# test_eyes.net
KiCad netlist of a schematic drawn in EAGLE
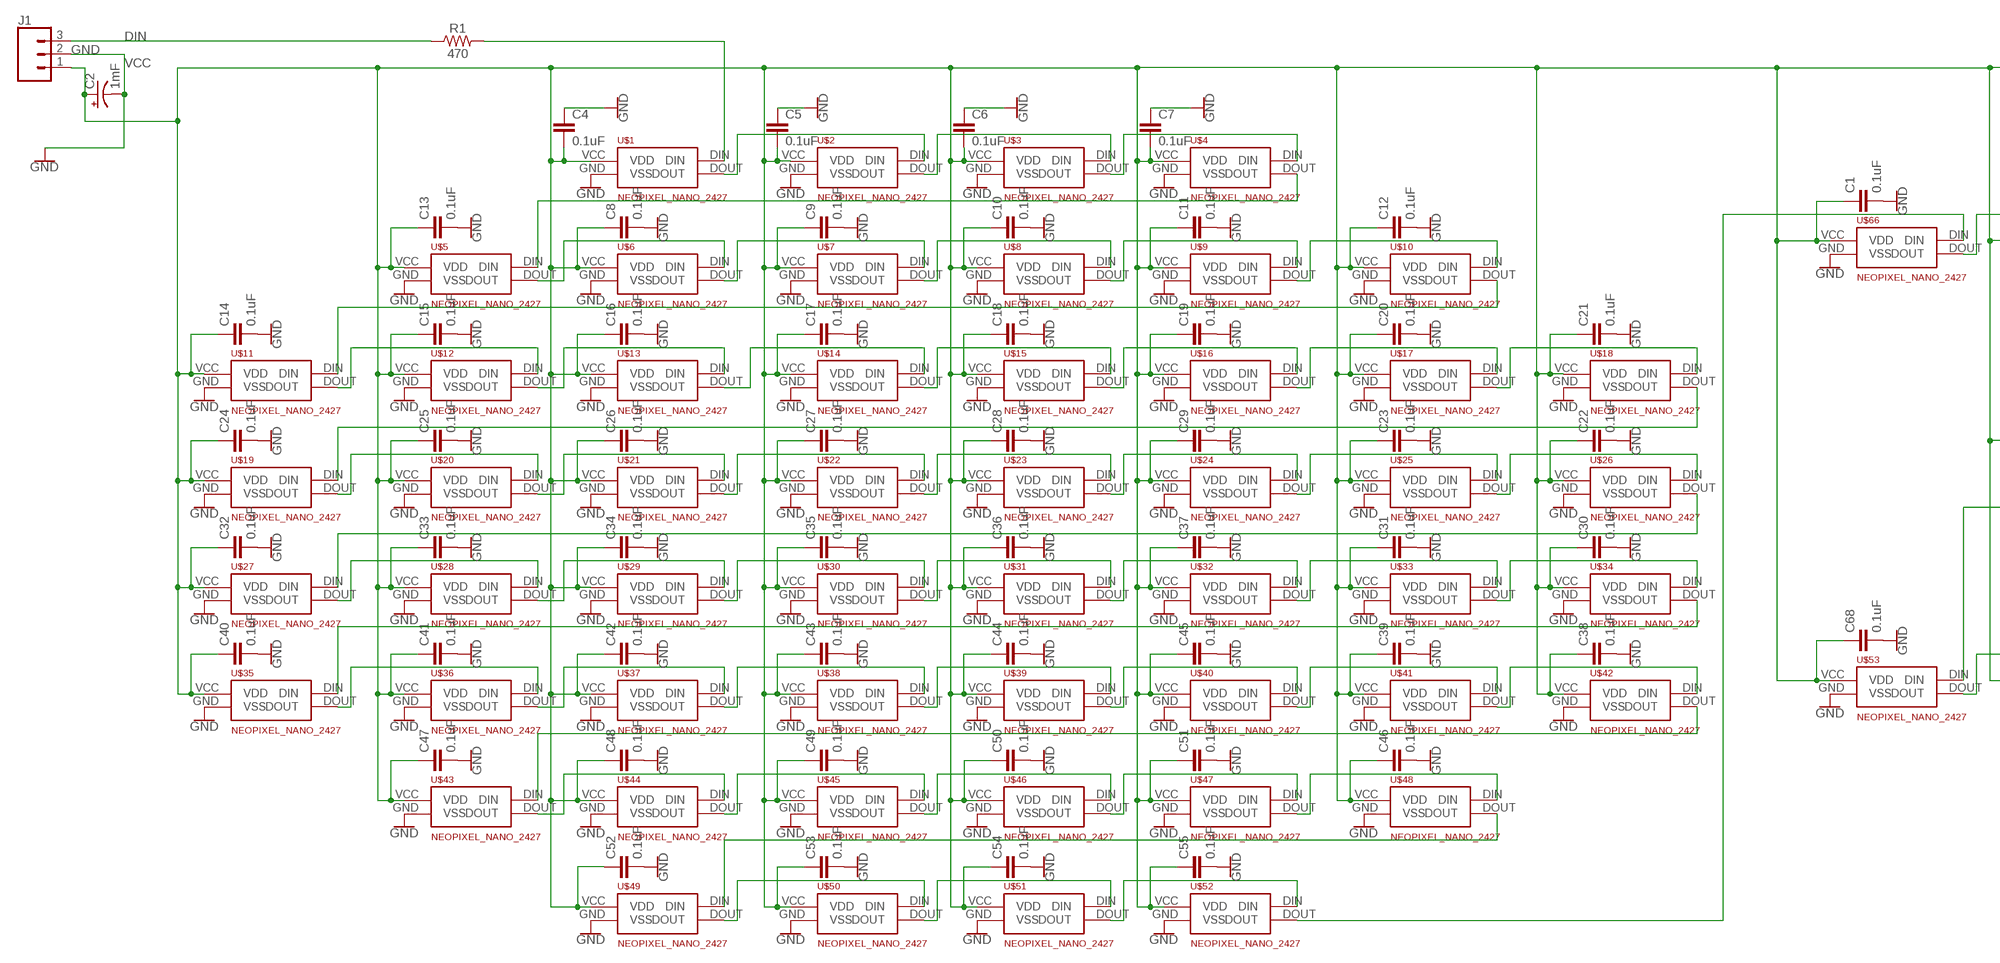
[diagram p0: schematic, sheet 1, part 1 of 3]
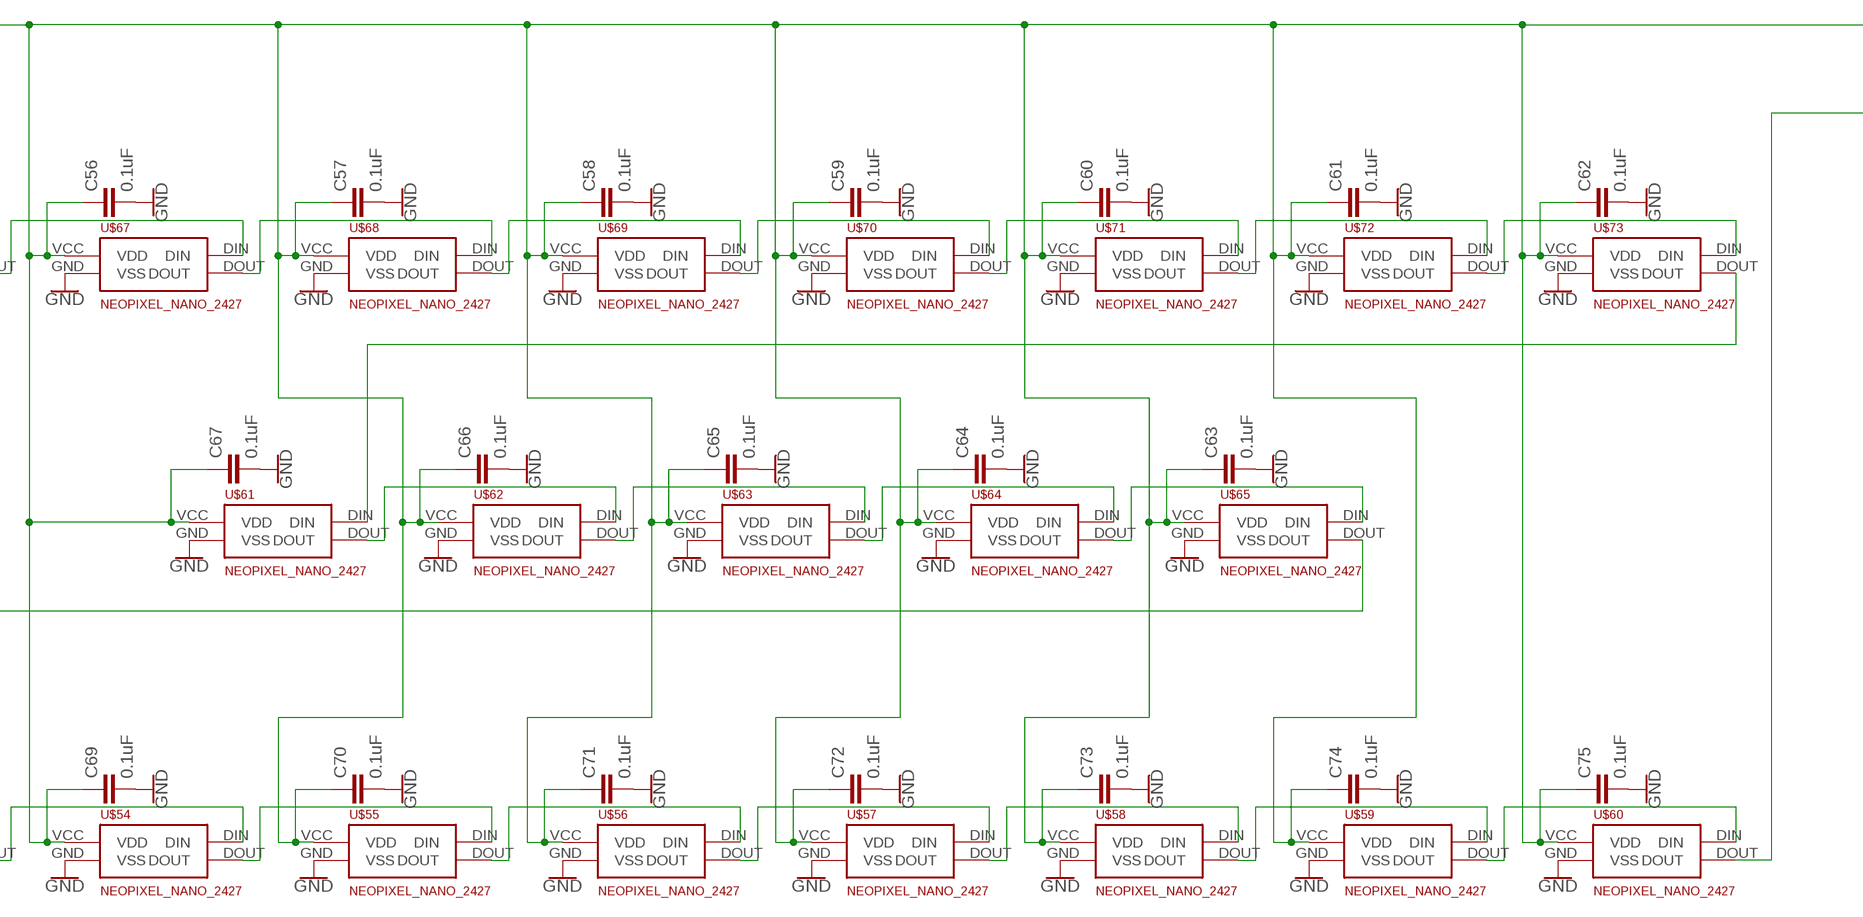
[diagram p1: schematic, sheet 1, part 2 of 3]
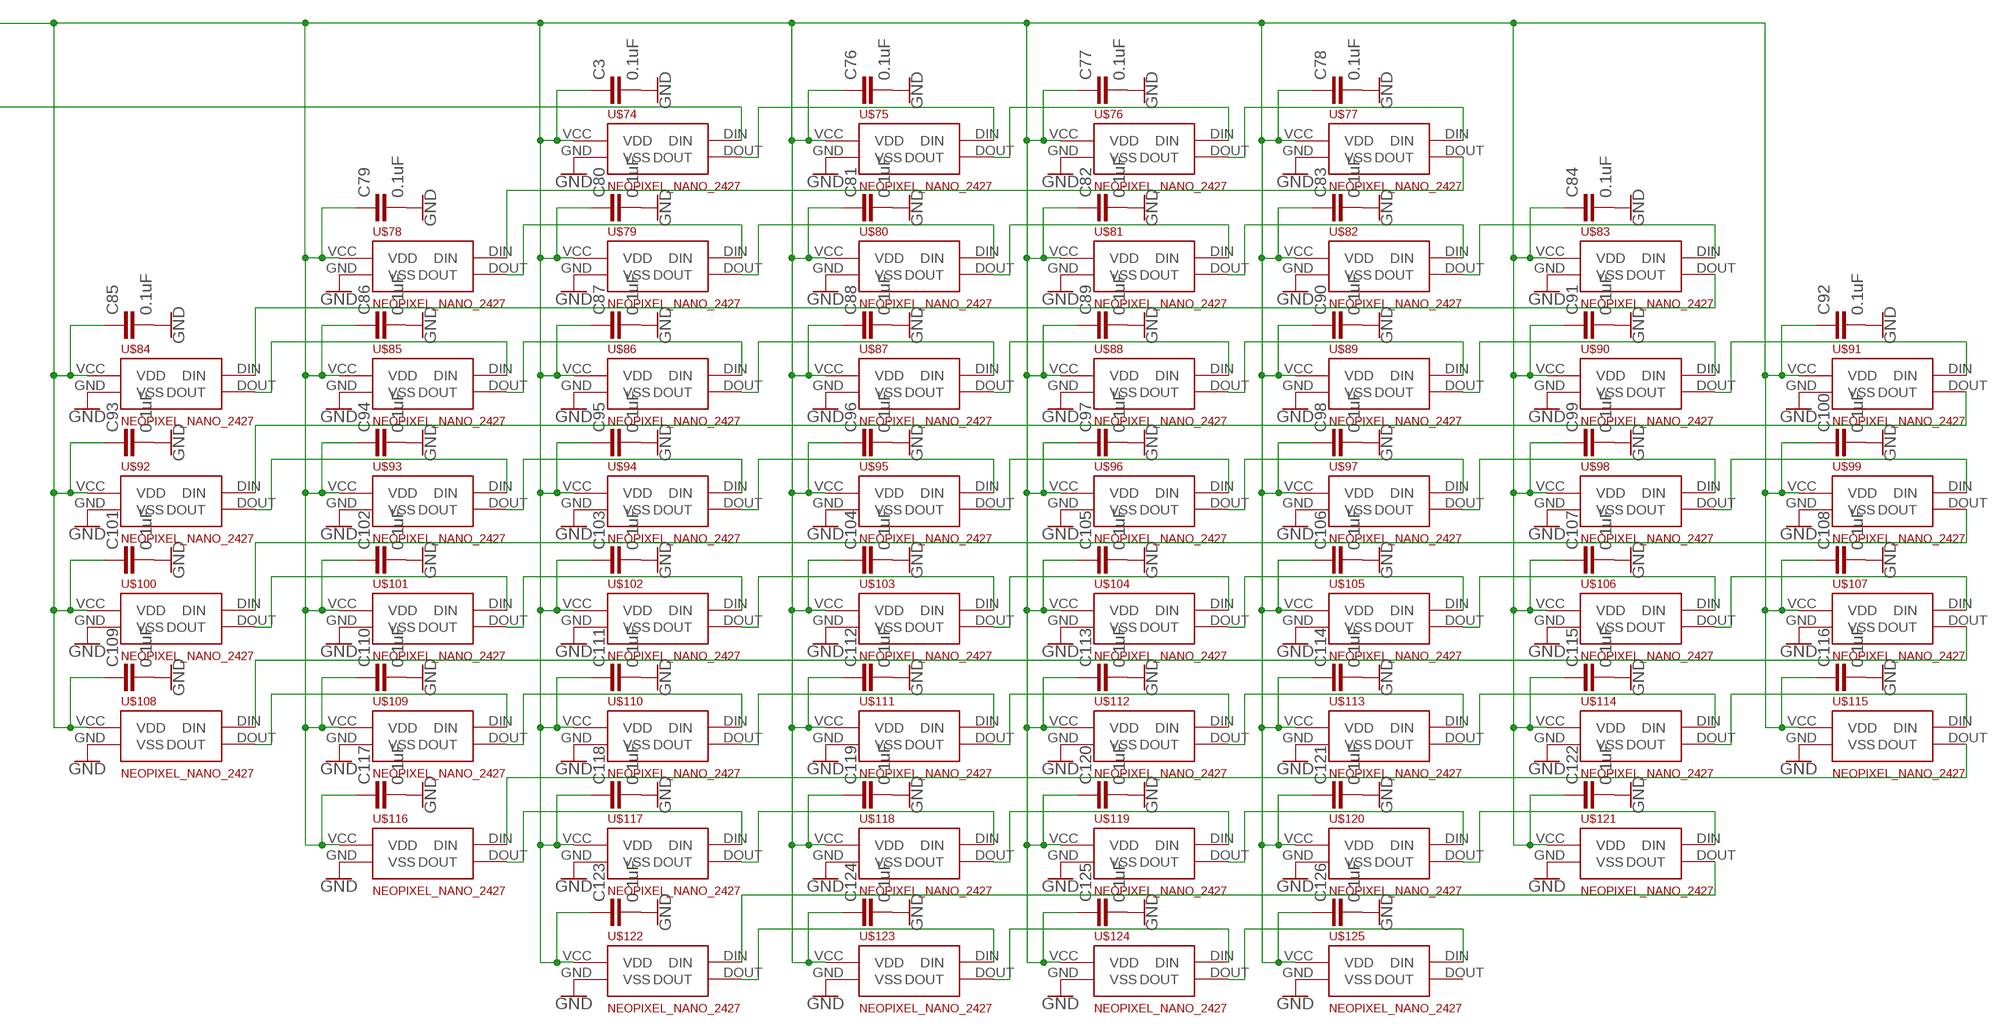
[diagram p2: schematic, sheet 1, part 3 of 3]

(export (version "E")
  (design (tool "Eeschema 10.0.6"))
  (components
    (comp (ref "C1")
      (value "0.1uF")
      (footprint "eagle-import:0402")
      (libsource (lib "eagle-import") (part "0.1UF-0402-16V-10%"))
    )
    (comp (ref "C2")
      (value "1mF")
      (footprint "eagle-import:CPOL-RADIAL-5MM-10MM")
      (libsource (lib "eagle-import") (part "1000UF-RADIAL-5MM-25V-20%"))
    )
    (comp (ref "C3")
      (value "0.1uF")
      (footprint "eagle-import:0402")
      (libsource (lib "eagle-import") (part "0.1UF-0402-16V-10%"))
    )
    (comp (ref "C4")
      (value "0.1uF")
      (footprint "eagle-import:0402")
      (libsource (lib "eagle-import") (part "0.1UF-0402-16V-10%"))
    )
    (comp (ref "C5")
      (value "0.1uF")
      (footprint "eagle-import:0402")
      (libsource (lib "eagle-import") (part "0.1UF-0402-16V-10%"))
    )
    (comp (ref "C6")
      (value "0.1uF")
      (footprint "eagle-import:0402")
      (libsource (lib "eagle-import") (part "0.1UF-0402-16V-10%"))
    )
    (comp (ref "C7")
      (value "0.1uF")
      (footprint "eagle-import:0402")
      (libsource (lib "eagle-import") (part "0.1UF-0402-16V-10%"))
    )
    (comp (ref "C8")
      (value "0.1uF")
      (footprint "eagle-import:0402")
      (libsource (lib "eagle-import") (part "0.1UF-0402-16V-10%"))
    )
    (comp (ref "C9")
      (value "0.1uF")
      (footprint "eagle-import:0402")
      (libsource (lib "eagle-import") (part "0.1UF-0402-16V-10%"))
    )
    (comp (ref "C10")
      (value "0.1uF")
      (footprint "eagle-import:0402")
      (libsource (lib "eagle-import") (part "0.1UF-0402-16V-10%"))
    )
    (comp (ref "C11")
      (value "0.1uF")
      (footprint "eagle-import:0402")
      (libsource (lib "eagle-import") (part "0.1UF-0402-16V-10%"))
    )
    (comp (ref "C12")
      (value "0.1uF")
      (footprint "eagle-import:0402")
      (libsource (lib "eagle-import") (part "0.1UF-0402-16V-10%"))
    )
    (comp (ref "C13")
      (value "0.1uF")
      (footprint "eagle-import:0402")
      (libsource (lib "eagle-import") (part "0.1UF-0402-16V-10%"))
    )
    (comp (ref "C14")
      (value "0.1uF")
      (footprint "eagle-import:0402")
      (libsource (lib "eagle-import") (part "0.1UF-0402-16V-10%"))
    )
    (comp (ref "C15")
      (value "0.1uF")
      (footprint "eagle-import:0402")
      (libsource (lib "eagle-import") (part "0.1UF-0402-16V-10%"))
    )
    (comp (ref "C16")
      (value "0.1uF")
      (footprint "eagle-import:0402")
      (libsource (lib "eagle-import") (part "0.1UF-0402-16V-10%"))
    )
    (comp (ref "C17")
      (value "0.1uF")
      (footprint "eagle-import:0402")
      (libsource (lib "eagle-import") (part "0.1UF-0402-16V-10%"))
    )
    (comp (ref "C18")
      (value "0.1uF")
      (footprint "eagle-import:0402")
      (libsource (lib "eagle-import") (part "0.1UF-0402-16V-10%"))
    )
    (comp (ref "C19")
      (value "0.1uF")
      (footprint "eagle-import:0402")
      (libsource (lib "eagle-import") (part "0.1UF-0402-16V-10%"))
    )
    (comp (ref "C20")
      (value "0.1uF")
      (footprint "eagle-import:0402")
      (libsource (lib "eagle-import") (part "0.1UF-0402-16V-10%"))
    )
    (comp (ref "C21")
      (value "0.1uF")
      (footprint "eagle-import:0402")
      (libsource (lib "eagle-import") (part "0.1UF-0402-16V-10%"))
    )
    (comp (ref "C22")
      (value "0.1uF")
      (footprint "eagle-import:0402")
      (libsource (lib "eagle-import") (part "0.1UF-0402-16V-10%"))
    )
    (comp (ref "C23")
      (value "0.1uF")
      (footprint "eagle-import:0402")
      (libsource (lib "eagle-import") (part "0.1UF-0402-16V-10%"))
    )
    (comp (ref "C24")
      (value "0.1uF")
      (footprint "eagle-import:0402")
      (libsource (lib "eagle-import") (part "0.1UF-0402-16V-10%"))
    )
    (comp (ref "C25")
      (value "0.1uF")
      (footprint "eagle-import:0402")
      (libsource (lib "eagle-import") (part "0.1UF-0402-16V-10%"))
    )
    (comp (ref "C26")
      (value "0.1uF")
      (footprint "eagle-import:0402")
      (libsource (lib "eagle-import") (part "0.1UF-0402-16V-10%"))
    )
    (comp (ref "C27")
      (value "0.1uF")
      (footprint "eagle-import:0402")
      (libsource (lib "eagle-import") (part "0.1UF-0402-16V-10%"))
    )
    (comp (ref "C28")
      (value "0.1uF")
      (footprint "eagle-import:0402")
      (libsource (lib "eagle-import") (part "0.1UF-0402-16V-10%"))
    )
    (comp (ref "C29")
      (value "0.1uF")
      (footprint "eagle-import:0402")
      (libsource (lib "eagle-import") (part "0.1UF-0402-16V-10%"))
    )
    (comp (ref "C30")
      (value "0.1uF")
      (footprint "eagle-import:0402")
      (libsource (lib "eagle-import") (part "0.1UF-0402-16V-10%"))
    )
    (comp (ref "C31")
      (value "0.1uF")
      (footprint "eagle-import:0402")
      (libsource (lib "eagle-import") (part "0.1UF-0402-16V-10%"))
    )
    (comp (ref "C32")
      (value "0.1uF")
      (footprint "eagle-import:0402")
      (libsource (lib "eagle-import") (part "0.1UF-0402-16V-10%"))
    )
    (comp (ref "C33")
      (value "0.1uF")
      (footprint "eagle-import:0402")
      (libsource (lib "eagle-import") (part "0.1UF-0402-16V-10%"))
    )
    (comp (ref "C34")
      (value "0.1uF")
      (footprint "eagle-import:0402")
      (libsource (lib "eagle-import") (part "0.1UF-0402-16V-10%"))
    )
    (comp (ref "C35")
      (value "0.1uF")
      (footprint "eagle-import:0402")
      (libsource (lib "eagle-import") (part "0.1UF-0402-16V-10%"))
    )
    (comp (ref "C36")
      (value "0.1uF")
      (footprint "eagle-import:0402")
      (libsource (lib "eagle-import") (part "0.1UF-0402-16V-10%"))
    )
    (comp (ref "C37")
      (value "0.1uF")
      (footprint "eagle-import:0402")
      (libsource (lib "eagle-import") (part "0.1UF-0402-16V-10%"))
    )
    (comp (ref "C38")
      (value "0.1uF")
      (footprint "eagle-import:0402")
      (libsource (lib "eagle-import") (part "0.1UF-0402-16V-10%"))
    )
    (comp (ref "C39")
      (value "0.1uF")
      (footprint "eagle-import:0402")
      (libsource (lib "eagle-import") (part "0.1UF-0402-16V-10%"))
    )
    (comp (ref "C40")
      (value "0.1uF")
      (footprint "eagle-import:0402")
      (libsource (lib "eagle-import") (part "0.1UF-0402-16V-10%"))
    )
    (comp (ref "C41")
      (value "0.1uF")
      (footprint "eagle-import:0402")
      (libsource (lib "eagle-import") (part "0.1UF-0402-16V-10%"))
    )
    (comp (ref "C42")
      (value "0.1uF")
      (footprint "eagle-import:0402")
      (libsource (lib "eagle-import") (part "0.1UF-0402-16V-10%"))
    )
    (comp (ref "C43")
      (value "0.1uF")
      (footprint "eagle-import:0402")
      (libsource (lib "eagle-import") (part "0.1UF-0402-16V-10%"))
    )
    (comp (ref "C44")
      (value "0.1uF")
      (footprint "eagle-import:0402")
      (libsource (lib "eagle-import") (part "0.1UF-0402-16V-10%"))
    )
    (comp (ref "C45")
      (value "0.1uF")
      (footprint "eagle-import:0402")
      (libsource (lib "eagle-import") (part "0.1UF-0402-16V-10%"))
    )
    (comp (ref "C46")
      (value "0.1uF")
      (footprint "eagle-import:0402")
      (libsource (lib "eagle-import") (part "0.1UF-0402-16V-10%"))
    )
    (comp (ref "C47")
      (value "0.1uF")
      (footprint "eagle-import:0402")
      (libsource (lib "eagle-import") (part "0.1UF-0402-16V-10%"))
    )
    (comp (ref "C48")
      (value "0.1uF")
      (footprint "eagle-import:0402")
      (libsource (lib "eagle-import") (part "0.1UF-0402-16V-10%"))
    )
    (comp (ref "C49")
      (value "0.1uF")
      (footprint "eagle-import:0402")
      (libsource (lib "eagle-import") (part "0.1UF-0402-16V-10%"))
    )
    (comp (ref "C50")
      (value "0.1uF")
      (footprint "eagle-import:0402")
      (libsource (lib "eagle-import") (part "0.1UF-0402-16V-10%"))
    )
    (comp (ref "C51")
      (value "0.1uF")
      (footprint "eagle-import:0402")
      (libsource (lib "eagle-import") (part "0.1UF-0402-16V-10%"))
    )
    (comp (ref "C52")
      (value "0.1uF")
      (footprint "eagle-import:0402")
      (libsource (lib "eagle-import") (part "0.1UF-0402-16V-10%"))
    )
    (comp (ref "C53")
      (value "0.1uF")
      (footprint "eagle-import:0402")
      (libsource (lib "eagle-import") (part "0.1UF-0402-16V-10%"))
    )
    (comp (ref "C54")
      (value "0.1uF")
      (footprint "eagle-import:0402")
      (libsource (lib "eagle-import") (part "0.1UF-0402-16V-10%"))
    )
    (comp (ref "C55")
      (value "0.1uF")
      (footprint "eagle-import:0402")
      (libsource (lib "eagle-import") (part "0.1UF-0402-16V-10%"))
    )
    (comp (ref "C56")
      (value "0.1uF")
      (footprint "eagle-import:0402")
      (libsource (lib "eagle-import") (part "0.1UF-0402-16V-10%"))
    )
    (comp (ref "C57")
      (value "0.1uF")
      (footprint "eagle-import:0402")
      (libsource (lib "eagle-import") (part "0.1UF-0402-16V-10%"))
    )
    (comp (ref "C58")
      (value "0.1uF")
      (footprint "eagle-import:0402")
      (libsource (lib "eagle-import") (part "0.1UF-0402-16V-10%"))
    )
    (comp (ref "C59")
      (value "0.1uF")
      (footprint "eagle-import:0402")
      (libsource (lib "eagle-import") (part "0.1UF-0402-16V-10%"))
    )
    (comp (ref "C60")
      (value "0.1uF")
      (footprint "eagle-import:0402")
      (libsource (lib "eagle-import") (part "0.1UF-0402-16V-10%"))
    )
    (comp (ref "C61")
      (value "0.1uF")
      (footprint "eagle-import:0402")
      (libsource (lib "eagle-import") (part "0.1UF-0402-16V-10%"))
    )
    (comp (ref "C62")
      (value "0.1uF")
      (footprint "eagle-import:0402")
      (libsource (lib "eagle-import") (part "0.1UF-0402-16V-10%"))
    )
    (comp (ref "C63")
      (value "0.1uF")
      (footprint "eagle-import:0402")
      (libsource (lib "eagle-import") (part "0.1UF-0402-16V-10%"))
    )
    (comp (ref "C64")
      (value "0.1uF")
      (footprint "eagle-import:0402")
      (libsource (lib "eagle-import") (part "0.1UF-0402-16V-10%"))
    )
    (comp (ref "C65")
      (value "0.1uF")
      (footprint "eagle-import:0402")
      (libsource (lib "eagle-import") (part "0.1UF-0402-16V-10%"))
    )
    (comp (ref "C66")
      (value "0.1uF")
      (footprint "eagle-import:0402")
      (libsource (lib "eagle-import") (part "0.1UF-0402-16V-10%"))
    )
    (comp (ref "C67")
      (value "0.1uF")
      (footprint "eagle-import:0402")
      (libsource (lib "eagle-import") (part "0.1UF-0402-16V-10%"))
    )
    (comp (ref "C68")
      (value "0.1uF")
      (footprint "eagle-import:0402")
      (libsource (lib "eagle-import") (part "0.1UF-0402-16V-10%"))
    )
    (comp (ref "C69")
      (value "0.1uF")
      (footprint "eagle-import:0402")
      (libsource (lib "eagle-import") (part "0.1UF-0402-16V-10%"))
    )
    (comp (ref "C70")
      (value "0.1uF")
      (footprint "eagle-import:0402")
      (libsource (lib "eagle-import") (part "0.1UF-0402-16V-10%"))
    )
    (comp (ref "C71")
      (value "0.1uF")
      (footprint "eagle-import:0402")
      (libsource (lib "eagle-import") (part "0.1UF-0402-16V-10%"))
    )
    (comp (ref "C72")
      (value "0.1uF")
      (footprint "eagle-import:0402")
      (libsource (lib "eagle-import") (part "0.1UF-0402-16V-10%"))
    )
    (comp (ref "C73")
      (value "0.1uF")
      (footprint "eagle-import:0402")
      (libsource (lib "eagle-import") (part "0.1UF-0402-16V-10%"))
    )
    (comp (ref "C74")
      (value "0.1uF")
      (footprint "eagle-import:0402")
      (libsource (lib "eagle-import") (part "0.1UF-0402-16V-10%"))
    )
    (comp (ref "C75")
      (value "0.1uF")
      (footprint "eagle-import:0402")
      (libsource (lib "eagle-import") (part "0.1UF-0402-16V-10%"))
    )
    (comp (ref "C76")
      (value "0.1uF")
      (footprint "eagle-import:0402")
      (libsource (lib "eagle-import") (part "0.1UF-0402-16V-10%"))
    )
    (comp (ref "C77")
      (value "0.1uF")
      (footprint "eagle-import:0402")
      (libsource (lib "eagle-import") (part "0.1UF-0402-16V-10%"))
    )
    (comp (ref "C78")
      (value "0.1uF")
      (footprint "eagle-import:0402")
      (libsource (lib "eagle-import") (part "0.1UF-0402-16V-10%"))
    )
    (comp (ref "C79")
      (value "0.1uF")
      (footprint "eagle-import:0402")
      (libsource (lib "eagle-import") (part "0.1UF-0402-16V-10%"))
    )
    (comp (ref "C80")
      (value "0.1uF")
      (footprint "eagle-import:0402")
      (libsource (lib "eagle-import") (part "0.1UF-0402-16V-10%"))
    )
    (comp (ref "C81")
      (value "0.1uF")
      (footprint "eagle-import:0402")
      (libsource (lib "eagle-import") (part "0.1UF-0402-16V-10%"))
    )
    (comp (ref "C82")
      (value "0.1uF")
      (footprint "eagle-import:0402")
      (libsource (lib "eagle-import") (part "0.1UF-0402-16V-10%"))
    )
    (comp (ref "C83")
      (value "0.1uF")
      (footprint "eagle-import:0402")
      (libsource (lib "eagle-import") (part "0.1UF-0402-16V-10%"))
    )
    (comp (ref "C84")
      (value "0.1uF")
      (footprint "eagle-import:0402")
      (libsource (lib "eagle-import") (part "0.1UF-0402-16V-10%"))
    )
    (comp (ref "C85")
      (value "0.1uF")
      (footprint "eagle-import:0402")
      (libsource (lib "eagle-import") (part "0.1UF-0402-16V-10%"))
    )
    (comp (ref "C86")
      (value "0.1uF")
      (footprint "eagle-import:0402")
      (libsource (lib "eagle-import") (part "0.1UF-0402-16V-10%"))
    )
    (comp (ref "C87")
      (value "0.1uF")
      (footprint "eagle-import:0402")
      (libsource (lib "eagle-import") (part "0.1UF-0402-16V-10%"))
    )
    (comp (ref "C88")
      (value "0.1uF")
      (footprint "eagle-import:0402")
      (libsource (lib "eagle-import") (part "0.1UF-0402-16V-10%"))
    )
    (comp (ref "C89")
      (value "0.1uF")
      (footprint "eagle-import:0402")
      (libsource (lib "eagle-import") (part "0.1UF-0402-16V-10%"))
    )
    (comp (ref "C90")
      (value "0.1uF")
      (footprint "eagle-import:0402")
      (libsource (lib "eagle-import") (part "0.1UF-0402-16V-10%"))
    )
    (comp (ref "C91")
      (value "0.1uF")
      (footprint "eagle-import:0402")
      (libsource (lib "eagle-import") (part "0.1UF-0402-16V-10%"))
    )
    (comp (ref "C92")
      (value "0.1uF")
      (footprint "eagle-import:0402")
      (libsource (lib "eagle-import") (part "0.1UF-0402-16V-10%"))
    )
    (comp (ref "C93")
      (value "0.1uF")
      (footprint "eagle-import:0402")
      (libsource (lib "eagle-import") (part "0.1UF-0402-16V-10%"))
    )
    (comp (ref "C94")
      (value "0.1uF")
      (footprint "eagle-import:0402")
      (libsource (lib "eagle-import") (part "0.1UF-0402-16V-10%"))
    )
    (comp (ref "C95")
      (value "0.1uF")
      (footprint "eagle-import:0402")
      (libsource (lib "eagle-import") (part "0.1UF-0402-16V-10%"))
    )
    (comp (ref "C96")
      (value "0.1uF")
      (footprint "eagle-import:0402")
      (libsource (lib "eagle-import") (part "0.1UF-0402-16V-10%"))
    )
    (comp (ref "C97")
      (value "0.1uF")
      (footprint "eagle-import:0402")
      (libsource (lib "eagle-import") (part "0.1UF-0402-16V-10%"))
    )
    (comp (ref "C98")
      (value "0.1uF")
      (footprint "eagle-import:0402")
      (libsource (lib "eagle-import") (part "0.1UF-0402-16V-10%"))
    )
    (comp (ref "C99")
      (value "0.1uF")
      (footprint "eagle-import:0402")
      (libsource (lib "eagle-import") (part "0.1UF-0402-16V-10%"))
    )
    (comp (ref "C100")
      (value "0.1uF")
      (footprint "eagle-import:0402")
      (libsource (lib "eagle-import") (part "0.1UF-0402-16V-10%"))
    )
    (comp (ref "C101")
      (value "0.1uF")
      (footprint "eagle-import:0402")
      (libsource (lib "eagle-import") (part "0.1UF-0402-16V-10%"))
    )
    (comp (ref "C102")
      (value "0.1uF")
      (footprint "eagle-import:0402")
      (libsource (lib "eagle-import") (part "0.1UF-0402-16V-10%"))
    )
    (comp (ref "C103")
      (value "0.1uF")
      (footprint "eagle-import:0402")
      (libsource (lib "eagle-import") (part "0.1UF-0402-16V-10%"))
    )
    (comp (ref "C104")
      (value "0.1uF")
      (footprint "eagle-import:0402")
      (libsource (lib "eagle-import") (part "0.1UF-0402-16V-10%"))
    )
    (comp (ref "C105")
      (value "0.1uF")
      (footprint "eagle-import:0402")
      (libsource (lib "eagle-import") (part "0.1UF-0402-16V-10%"))
    )
    (comp (ref "C106")
      (value "0.1uF")
      (footprint "eagle-import:0402")
      (libsource (lib "eagle-import") (part "0.1UF-0402-16V-10%"))
    )
    (comp (ref "C107")
      (value "0.1uF")
      (footprint "eagle-import:0402")
      (libsource (lib "eagle-import") (part "0.1UF-0402-16V-10%"))
    )
    (comp (ref "C108")
      (value "0.1uF")
      (footprint "eagle-import:0402")
      (libsource (lib "eagle-import") (part "0.1UF-0402-16V-10%"))
    )
    (comp (ref "C109")
      (value "0.1uF")
      (footprint "eagle-import:0402")
      (libsource (lib "eagle-import") (part "0.1UF-0402-16V-10%"))
    )
    (comp (ref "C110")
      (value "0.1uF")
      (footprint "eagle-import:0402")
      (libsource (lib "eagle-import") (part "0.1UF-0402-16V-10%"))
    )
    (comp (ref "C111")
      (value "0.1uF")
      (footprint "eagle-import:0402")
      (libsource (lib "eagle-import") (part "0.1UF-0402-16V-10%"))
    )
    (comp (ref "C112")
      (value "0.1uF")
      (footprint "eagle-import:0402")
      (libsource (lib "eagle-import") (part "0.1UF-0402-16V-10%"))
    )
    (comp (ref "C113")
      (value "0.1uF")
      (footprint "eagle-import:0402")
      (libsource (lib "eagle-import") (part "0.1UF-0402-16V-10%"))
    )
    (comp (ref "C114")
      (value "0.1uF")
      (footprint "eagle-import:0402")
      (libsource (lib "eagle-import") (part "0.1UF-0402-16V-10%"))
    )
    (comp (ref "C115")
      (value "0.1uF")
      (footprint "eagle-import:0402")
      (libsource (lib "eagle-import") (part "0.1UF-0402-16V-10%"))
    )
    (comp (ref "C116")
      (value "0.1uF")
      (footprint "eagle-import:0402")
      (libsource (lib "eagle-import") (part "0.1UF-0402-16V-10%"))
    )
    (comp (ref "C117")
      (value "0.1uF")
      (footprint "eagle-import:0402")
      (libsource (lib "eagle-import") (part "0.1UF-0402-16V-10%"))
    )
    (comp (ref "C118")
      (value "0.1uF")
      (footprint "eagle-import:0402")
      (libsource (lib "eagle-import") (part "0.1UF-0402-16V-10%"))
    )
    (comp (ref "C119")
      (value "0.1uF")
      (footprint "eagle-import:0402")
      (libsource (lib "eagle-import") (part "0.1UF-0402-16V-10%"))
    )
    (comp (ref "C120")
      (value "0.1uF")
      (footprint "eagle-import:0402")
      (libsource (lib "eagle-import") (part "0.1UF-0402-16V-10%"))
    )
    (comp (ref "C121")
      (value "0.1uF")
      (footprint "eagle-import:0402")
      (libsource (lib "eagle-import") (part "0.1UF-0402-16V-10%"))
    )
    (comp (ref "C122")
      (value "0.1uF")
      (footprint "eagle-import:0402")
      (libsource (lib "eagle-import") (part "0.1UF-0402-16V-10%"))
    )
    (comp (ref "C123")
      (value "0.1uF")
      (footprint "eagle-import:0402")
      (libsource (lib "eagle-import") (part "0.1UF-0402-16V-10%"))
    )
    (comp (ref "C124")
      (value "0.1uF")
      (footprint "eagle-import:0402")
      (libsource (lib "eagle-import") (part "0.1UF-0402-16V-10%"))
    )
    (comp (ref "C125")
      (value "0.1uF")
      (footprint "eagle-import:0402")
      (libsource (lib "eagle-import") (part "0.1UF-0402-16V-10%"))
    )
    (comp (ref "C126")
      (value "0.1uF")
      (footprint "eagle-import:0402")
      (libsource (lib "eagle-import") (part "0.1UF-0402-16V-10%"))
    )
    (comp (ref "J1")
      (value "CONN_03JST-PTH-VERT")
      (footprint "eagle-import:JST-3-PTH-VERT")
      (libsource (lib "eagle-import") (part "CONN_03JST-PTH-VERT"))
    )
    (comp (ref "R1")
      (value "470")
      (footprint "eagle-import:0603")
      (libsource (lib "eagle-import") (part "470OHM-0603-1/10W-1%"))
    )
    (comp (ref "U$1")
      (value "NEOPIXEL_NANO_2427")
      (footprint "eagle-import:SK6805-2427")
      (libsource (lib "eagle-import") (part "NEOPIXEL_NANO_2427"))
    )
    (comp (ref "U$2")
      (value "NEOPIXEL_NANO_2427")
      (footprint "eagle-import:SK6805-2427")
      (libsource (lib "eagle-import") (part "NEOPIXEL_NANO_2427"))
    )
    (comp (ref "U$3")
      (value "NEOPIXEL_NANO_2427")
      (footprint "eagle-import:SK6805-2427")
      (libsource (lib "eagle-import") (part "NEOPIXEL_NANO_2427"))
    )
    (comp (ref "U$4")
      (value "NEOPIXEL_NANO_2427")
      (footprint "eagle-import:SK6805-2427")
      (libsource (lib "eagle-import") (part "NEOPIXEL_NANO_2427"))
    )
    (comp (ref "U$5")
      (value "NEOPIXEL_NANO_2427")
      (footprint "eagle-import:SK6805-2427")
      (libsource (lib "eagle-import") (part "NEOPIXEL_NANO_2427"))
    )
    (comp (ref "U$6")
      (value "NEOPIXEL_NANO_2427")
      (footprint "eagle-import:SK6805-2427")
      (libsource (lib "eagle-import") (part "NEOPIXEL_NANO_2427"))
    )
    (comp (ref "U$7")
      (value "NEOPIXEL_NANO_2427")
      (footprint "eagle-import:SK6805-2427")
      (libsource (lib "eagle-import") (part "NEOPIXEL_NANO_2427"))
    )
    (comp (ref "U$8")
      (value "NEOPIXEL_NANO_2427")
      (footprint "eagle-import:SK6805-2427")
      (libsource (lib "eagle-import") (part "NEOPIXEL_NANO_2427"))
    )
    (comp (ref "U$9")
      (value "NEOPIXEL_NANO_2427")
      (footprint "eagle-import:SK6805-2427")
      (libsource (lib "eagle-import") (part "NEOPIXEL_NANO_2427"))
    )
    (comp (ref "U$10")
      (value "NEOPIXEL_NANO_2427")
      (footprint "eagle-import:SK6805-2427")
      (libsource (lib "eagle-import") (part "NEOPIXEL_NANO_2427"))
    )
    (comp (ref "U$11")
      (value "NEOPIXEL_NANO_2427")
      (footprint "eagle-import:SK6805-2427")
      (libsource (lib "eagle-import") (part "NEOPIXEL_NANO_2427"))
    )
    (comp (ref "U$12")
      (value "NEOPIXEL_NANO_2427")
      (footprint "eagle-import:SK6805-2427")
      (libsource (lib "eagle-import") (part "NEOPIXEL_NANO_2427"))
    )
    (comp (ref "U$13")
      (value "NEOPIXEL_NANO_2427")
      (footprint "eagle-import:SK6805-2427")
      (libsource (lib "eagle-import") (part "NEOPIXEL_NANO_2427"))
    )
    (comp (ref "U$14")
      (value "NEOPIXEL_NANO_2427")
      (footprint "eagle-import:SK6805-2427")
      (libsource (lib "eagle-import") (part "NEOPIXEL_NANO_2427"))
    )
    (comp (ref "U$15")
      (value "NEOPIXEL_NANO_2427")
      (footprint "eagle-import:SK6805-2427")
      (libsource (lib "eagle-import") (part "NEOPIXEL_NANO_2427"))
    )
    (comp (ref "U$16")
      (value "NEOPIXEL_NANO_2427")
      (footprint "eagle-import:SK6805-2427")
      (libsource (lib "eagle-import") (part "NEOPIXEL_NANO_2427"))
    )
    (comp (ref "U$17")
      (value "NEOPIXEL_NANO_2427")
      (footprint "eagle-import:SK6805-2427")
      (libsource (lib "eagle-import") (part "NEOPIXEL_NANO_2427"))
    )
    (comp (ref "U$18")
      (value "NEOPIXEL_NANO_2427")
      (footprint "eagle-import:SK6805-2427")
      (libsource (lib "eagle-import") (part "NEOPIXEL_NANO_2427"))
    )
    (comp (ref "U$19")
      (value "NEOPIXEL_NANO_2427")
      (footprint "eagle-import:SK6805-2427")
      (libsource (lib "eagle-import") (part "NEOPIXEL_NANO_2427"))
    )
    (comp (ref "U$20")
      (value "NEOPIXEL_NANO_2427")
      (footprint "eagle-import:SK6805-2427")
      (libsource (lib "eagle-import") (part "NEOPIXEL_NANO_2427"))
    )
    (comp (ref "U$21")
      (value "NEOPIXEL_NANO_2427")
      (footprint "eagle-import:SK6805-2427")
      (libsource (lib "eagle-import") (part "NEOPIXEL_NANO_2427"))
    )
    (comp (ref "U$22")
      (value "NEOPIXEL_NANO_2427")
      (footprint "eagle-import:SK6805-2427")
      (libsource (lib "eagle-import") (part "NEOPIXEL_NANO_2427"))
    )
    (comp (ref "U$23")
      (value "NEOPIXEL_NANO_2427")
      (footprint "eagle-import:SK6805-2427")
      (libsource (lib "eagle-import") (part "NEOPIXEL_NANO_2427"))
    )
    (comp (ref "U$24")
      (value "NEOPIXEL_NANO_2427")
      (footprint "eagle-import:SK6805-2427")
      (libsource (lib "eagle-import") (part "NEOPIXEL_NANO_2427"))
    )
    (comp (ref "U$25")
      (value "NEOPIXEL_NANO_2427")
      (footprint "eagle-import:SK6805-2427")
      (libsource (lib "eagle-import") (part "NEOPIXEL_NANO_2427"))
    )
    (comp (ref "U$26")
      (value "NEOPIXEL_NANO_2427")
      (footprint "eagle-import:SK6805-2427")
      (libsource (lib "eagle-import") (part "NEOPIXEL_NANO_2427"))
    )
    (comp (ref "U$27")
      (value "NEOPIXEL_NANO_2427")
      (footprint "eagle-import:SK6805-2427")
      (libsource (lib "eagle-import") (part "NEOPIXEL_NANO_2427"))
    )
    (comp (ref "U$28")
      (value "NEOPIXEL_NANO_2427")
      (footprint "eagle-import:SK6805-2427")
      (libsource (lib "eagle-import") (part "NEOPIXEL_NANO_2427"))
    )
    (comp (ref "U$29")
      (value "NEOPIXEL_NANO_2427")
      (footprint "eagle-import:SK6805-2427")
      (libsource (lib "eagle-import") (part "NEOPIXEL_NANO_2427"))
    )
    (comp (ref "U$30")
      (value "NEOPIXEL_NANO_2427")
      (footprint "eagle-import:SK6805-2427")
      (libsource (lib "eagle-import") (part "NEOPIXEL_NANO_2427"))
    )
    (comp (ref "U$31")
      (value "NEOPIXEL_NANO_2427")
      (footprint "eagle-import:SK6805-2427")
      (libsource (lib "eagle-import") (part "NEOPIXEL_NANO_2427"))
    )
    (comp (ref "U$32")
      (value "NEOPIXEL_NANO_2427")
      (footprint "eagle-import:SK6805-2427")
      (libsource (lib "eagle-import") (part "NEOPIXEL_NANO_2427"))
    )
    (comp (ref "U$33")
      (value "NEOPIXEL_NANO_2427")
      (footprint "eagle-import:SK6805-2427")
      (libsource (lib "eagle-import") (part "NEOPIXEL_NANO_2427"))
    )
    (comp (ref "U$34")
      (value "NEOPIXEL_NANO_2427")
      (footprint "eagle-import:SK6805-2427")
      (libsource (lib "eagle-import") (part "NEOPIXEL_NANO_2427"))
    )
    (comp (ref "U$35")
      (value "NEOPIXEL_NANO_2427")
      (footprint "eagle-import:SK6805-2427")
      (libsource (lib "eagle-import") (part "NEOPIXEL_NANO_2427"))
    )
    (comp (ref "U$36")
      (value "NEOPIXEL_NANO_2427")
      (footprint "eagle-import:SK6805-2427")
      (libsource (lib "eagle-import") (part "NEOPIXEL_NANO_2427"))
    )
    (comp (ref "U$37")
      (value "NEOPIXEL_NANO_2427")
      (footprint "eagle-import:SK6805-2427")
      (libsource (lib "eagle-import") (part "NEOPIXEL_NANO_2427"))
    )
    (comp (ref "U$38")
      (value "NEOPIXEL_NANO_2427")
      (footprint "eagle-import:SK6805-2427")
      (libsource (lib "eagle-import") (part "NEOPIXEL_NANO_2427"))
    )
    (comp (ref "U$39")
      (value "NEOPIXEL_NANO_2427")
      (footprint "eagle-import:SK6805-2427")
      (libsource (lib "eagle-import") (part "NEOPIXEL_NANO_2427"))
    )
    (comp (ref "U$40")
      (value "NEOPIXEL_NANO_2427")
      (footprint "eagle-import:SK6805-2427")
      (libsource (lib "eagle-import") (part "NEOPIXEL_NANO_2427"))
    )
    (comp (ref "U$41")
      (value "NEOPIXEL_NANO_2427")
      (footprint "eagle-import:SK6805-2427")
      (libsource (lib "eagle-import") (part "NEOPIXEL_NANO_2427"))
    )
    (comp (ref "U$42")
      (value "NEOPIXEL_NANO_2427")
      (footprint "eagle-import:SK6805-2427")
      (libsource (lib "eagle-import") (part "NEOPIXEL_NANO_2427"))
    )
    (comp (ref "U$43")
      (value "NEOPIXEL_NANO_2427")
      (footprint "eagle-import:SK6805-2427")
      (libsource (lib "eagle-import") (part "NEOPIXEL_NANO_2427"))
    )
    (comp (ref "U$44")
      (value "NEOPIXEL_NANO_2427")
      (footprint "eagle-import:SK6805-2427")
      (libsource (lib "eagle-import") (part "NEOPIXEL_NANO_2427"))
    )
    (comp (ref "U$45")
      (value "NEOPIXEL_NANO_2427")
      (footprint "eagle-import:SK6805-2427")
      (libsource (lib "eagle-import") (part "NEOPIXEL_NANO_2427"))
    )
    (comp (ref "U$46")
      (value "NEOPIXEL_NANO_2427")
      (footprint "eagle-import:SK6805-2427")
      (libsource (lib "eagle-import") (part "NEOPIXEL_NANO_2427"))
    )
    (comp (ref "U$47")
      (value "NEOPIXEL_NANO_2427")
      (footprint "eagle-import:SK6805-2427")
      (libsource (lib "eagle-import") (part "NEOPIXEL_NANO_2427"))
    )
    (comp (ref "U$48")
      (value "NEOPIXEL_NANO_2427")
      (footprint "eagle-import:SK6805-2427")
      (libsource (lib "eagle-import") (part "NEOPIXEL_NANO_2427"))
    )
    (comp (ref "U$49")
      (value "NEOPIXEL_NANO_2427")
      (footprint "eagle-import:SK6805-2427")
      (libsource (lib "eagle-import") (part "NEOPIXEL_NANO_2427"))
    )
    (comp (ref "U$50")
      (value "NEOPIXEL_NANO_2427")
      (footprint "eagle-import:SK6805-2427")
      (libsource (lib "eagle-import") (part "NEOPIXEL_NANO_2427"))
    )
    (comp (ref "U$51")
      (value "NEOPIXEL_NANO_2427")
      (footprint "eagle-import:SK6805-2427")
      (libsource (lib "eagle-import") (part "NEOPIXEL_NANO_2427"))
    )
    (comp (ref "U$52")
      (value "NEOPIXEL_NANO_2427")
      (footprint "eagle-import:SK6805-2427")
      (libsource (lib "eagle-import") (part "NEOPIXEL_NANO_2427"))
    )
    (comp (ref "U$53")
      (value "NEOPIXEL_NANO_2427")
      (footprint "eagle-import:SK6805-2427")
      (libsource (lib "eagle-import") (part "NEOPIXEL_NANO_2427"))
    )
    (comp (ref "U$54")
      (value "NEOPIXEL_NANO_2427")
      (footprint "eagle-import:SK6805-2427")
      (libsource (lib "eagle-import") (part "NEOPIXEL_NANO_2427"))
    )
    (comp (ref "U$55")
      (value "NEOPIXEL_NANO_2427")
      (footprint "eagle-import:SK6805-2427")
      (libsource (lib "eagle-import") (part "NEOPIXEL_NANO_2427"))
    )
    (comp (ref "U$56")
      (value "NEOPIXEL_NANO_2427")
      (footprint "eagle-import:SK6805-2427")
      (libsource (lib "eagle-import") (part "NEOPIXEL_NANO_2427"))
    )
    (comp (ref "U$57")
      (value "NEOPIXEL_NANO_2427")
      (footprint "eagle-import:SK6805-2427")
      (libsource (lib "eagle-import") (part "NEOPIXEL_NANO_2427"))
    )
    (comp (ref "U$58")
      (value "NEOPIXEL_NANO_2427")
      (footprint "eagle-import:SK6805-2427")
      (libsource (lib "eagle-import") (part "NEOPIXEL_NANO_2427"))
    )
    (comp (ref "U$59")
      (value "NEOPIXEL_NANO_2427")
      (footprint "eagle-import:SK6805-2427")
      (libsource (lib "eagle-import") (part "NEOPIXEL_NANO_2427"))
    )
    (comp (ref "U$60")
      (value "NEOPIXEL_NANO_2427")
      (footprint "eagle-import:SK6805-2427")
      (libsource (lib "eagle-import") (part "NEOPIXEL_NANO_2427"))
    )
    (comp (ref "U$61")
      (value "NEOPIXEL_NANO_2427")
      (footprint "eagle-import:SK6805-2427")
      (libsource (lib "eagle-import") (part "NEOPIXEL_NANO_2427"))
    )
    (comp (ref "U$62")
      (value "NEOPIXEL_NANO_2427")
      (footprint "eagle-import:SK6805-2427")
      (libsource (lib "eagle-import") (part "NEOPIXEL_NANO_2427"))
    )
    (comp (ref "U$63")
      (value "NEOPIXEL_NANO_2427")
      (footprint "eagle-import:SK6805-2427")
      (libsource (lib "eagle-import") (part "NEOPIXEL_NANO_2427"))
    )
    (comp (ref "U$64")
      (value "NEOPIXEL_NANO_2427")
      (footprint "eagle-import:SK6805-2427")
      (libsource (lib "eagle-import") (part "NEOPIXEL_NANO_2427"))
    )
    (comp (ref "U$65")
      (value "NEOPIXEL_NANO_2427")
      (footprint "eagle-import:SK6805-2427")
      (libsource (lib "eagle-import") (part "NEOPIXEL_NANO_2427"))
    )
    (comp (ref "U$66")
      (value "NEOPIXEL_NANO_2427")
      (footprint "eagle-import:SK6805-2427")
      (libsource (lib "eagle-import") (part "NEOPIXEL_NANO_2427"))
    )
    (comp (ref "U$67")
      (value "NEOPIXEL_NANO_2427")
      (footprint "eagle-import:SK6805-2427")
      (libsource (lib "eagle-import") (part "NEOPIXEL_NANO_2427"))
    )
    (comp (ref "U$68")
      (value "NEOPIXEL_NANO_2427")
      (footprint "eagle-import:SK6805-2427")
      (libsource (lib "eagle-import") (part "NEOPIXEL_NANO_2427"))
    )
    (comp (ref "U$69")
      (value "NEOPIXEL_NANO_2427")
      (footprint "eagle-import:SK6805-2427")
      (libsource (lib "eagle-import") (part "NEOPIXEL_NANO_2427"))
    )
    (comp (ref "U$70")
      (value "NEOPIXEL_NANO_2427")
      (footprint "eagle-import:SK6805-2427")
      (libsource (lib "eagle-import") (part "NEOPIXEL_NANO_2427"))
    )
    (comp (ref "U$71")
      (value "NEOPIXEL_NANO_2427")
      (footprint "eagle-import:SK6805-2427")
      (libsource (lib "eagle-import") (part "NEOPIXEL_NANO_2427"))
    )
    (comp (ref "U$72")
      (value "NEOPIXEL_NANO_2427")
      (footprint "eagle-import:SK6805-2427")
      (libsource (lib "eagle-import") (part "NEOPIXEL_NANO_2427"))
    )
    (comp (ref "U$73")
      (value "NEOPIXEL_NANO_2427")
      (footprint "eagle-import:SK6805-2427")
      (libsource (lib "eagle-import") (part "NEOPIXEL_NANO_2427"))
    )
    (comp (ref "U$74")
      (value "NEOPIXEL_NANO_2427")
      (footprint "eagle-import:SK6805-2427")
      (libsource (lib "eagle-import") (part "NEOPIXEL_NANO_2427"))
    )
    (comp (ref "U$75")
      (value "NEOPIXEL_NANO_2427")
      (footprint "eagle-import:SK6805-2427")
      (libsource (lib "eagle-import") (part "NEOPIXEL_NANO_2427"))
    )
    (comp (ref "U$76")
      (value "NEOPIXEL_NANO_2427")
      (footprint "eagle-import:SK6805-2427")
      (libsource (lib "eagle-import") (part "NEOPIXEL_NANO_2427"))
    )
    (comp (ref "U$77")
      (value "NEOPIXEL_NANO_2427")
      (footprint "eagle-import:SK6805-2427")
      (libsource (lib "eagle-import") (part "NEOPIXEL_NANO_2427"))
    )
    (comp (ref "U$78")
      (value "NEOPIXEL_NANO_2427")
      (footprint "eagle-import:SK6805-2427")
      (libsource (lib "eagle-import") (part "NEOPIXEL_NANO_2427"))
    )
    (comp (ref "U$79")
      (value "NEOPIXEL_NANO_2427")
      (footprint "eagle-import:SK6805-2427")
      (libsource (lib "eagle-import") (part "NEOPIXEL_NANO_2427"))
    )
    (comp (ref "U$80")
      (value "NEOPIXEL_NANO_2427")
      (footprint "eagle-import:SK6805-2427")
      (libsource (lib "eagle-import") (part "NEOPIXEL_NANO_2427"))
    )
    (comp (ref "U$81")
      (value "NEOPIXEL_NANO_2427")
      (footprint "eagle-import:SK6805-2427")
      (libsource (lib "eagle-import") (part "NEOPIXEL_NANO_2427"))
    )
    (comp (ref "U$82")
      (value "NEOPIXEL_NANO_2427")
      (footprint "eagle-import:SK6805-2427")
      (libsource (lib "eagle-import") (part "NEOPIXEL_NANO_2427"))
    )
    (comp (ref "U$83")
      (value "NEOPIXEL_NANO_2427")
      (footprint "eagle-import:SK6805-2427")
      (libsource (lib "eagle-import") (part "NEOPIXEL_NANO_2427"))
    )
    (comp (ref "U$84")
      (value "NEOPIXEL_NANO_2427")
      (footprint "eagle-import:SK6805-2427")
      (libsource (lib "eagle-import") (part "NEOPIXEL_NANO_2427"))
    )
    (comp (ref "U$85")
      (value "NEOPIXEL_NANO_2427")
      (footprint "eagle-import:SK6805-2427")
      (libsource (lib "eagle-import") (part "NEOPIXEL_NANO_2427"))
    )
    (comp (ref "U$86")
      (value "NEOPIXEL_NANO_2427")
      (footprint "eagle-import:SK6805-2427")
      (libsource (lib "eagle-import") (part "NEOPIXEL_NANO_2427"))
    )
    (comp (ref "U$87")
      (value "NEOPIXEL_NANO_2427")
      (footprint "eagle-import:SK6805-2427")
      (libsource (lib "eagle-import") (part "NEOPIXEL_NANO_2427"))
    )
    (comp (ref "U$88")
      (value "NEOPIXEL_NANO_2427")
      (footprint "eagle-import:SK6805-2427")
      (libsource (lib "eagle-import") (part "NEOPIXEL_NANO_2427"))
    )
    (comp (ref "U$89")
      (value "NEOPIXEL_NANO_2427")
      (footprint "eagle-import:SK6805-2427")
      (libsource (lib "eagle-import") (part "NEOPIXEL_NANO_2427"))
    )
    (comp (ref "U$90")
      (value "NEOPIXEL_NANO_2427")
      (footprint "eagle-import:SK6805-2427")
      (libsource (lib "eagle-import") (part "NEOPIXEL_NANO_2427"))
    )
    (comp (ref "U$91")
      (value "NEOPIXEL_NANO_2427")
      (footprint "eagle-import:SK6805-2427")
      (libsource (lib "eagle-import") (part "NEOPIXEL_NANO_2427"))
    )
    (comp (ref "U$92")
      (value "NEOPIXEL_NANO_2427")
      (footprint "eagle-import:SK6805-2427")
      (libsource (lib "eagle-import") (part "NEOPIXEL_NANO_2427"))
    )
    (comp (ref "U$93")
      (value "NEOPIXEL_NANO_2427")
      (footprint "eagle-import:SK6805-2427")
      (libsource (lib "eagle-import") (part "NEOPIXEL_NANO_2427"))
    )
    (comp (ref "U$94")
      (value "NEOPIXEL_NANO_2427")
      (footprint "eagle-import:SK6805-2427")
      (libsource (lib "eagle-import") (part "NEOPIXEL_NANO_2427"))
    )
    (comp (ref "U$95")
      (value "NEOPIXEL_NANO_2427")
      (footprint "eagle-import:SK6805-2427")
      (libsource (lib "eagle-import") (part "NEOPIXEL_NANO_2427"))
    )
    (comp (ref "U$96")
      (value "NEOPIXEL_NANO_2427")
      (footprint "eagle-import:SK6805-2427")
      (libsource (lib "eagle-import") (part "NEOPIXEL_NANO_2427"))
    )
    (comp (ref "U$97")
      (value "NEOPIXEL_NANO_2427")
      (footprint "eagle-import:SK6805-2427")
      (libsource (lib "eagle-import") (part "NEOPIXEL_NANO_2427"))
    )
    (comp (ref "U$98")
      (value "NEOPIXEL_NANO_2427")
      (footprint "eagle-import:SK6805-2427")
      (libsource (lib "eagle-import") (part "NEOPIXEL_NANO_2427"))
    )
    (comp (ref "U$99")
      (value "NEOPIXEL_NANO_2427")
      (footprint "eagle-import:SK6805-2427")
      (libsource (lib "eagle-import") (part "NEOPIXEL_NANO_2427"))
    )
    (comp (ref "U$100")
      (value "NEOPIXEL_NANO_2427")
      (footprint "eagle-import:SK6805-2427")
      (libsource (lib "eagle-import") (part "NEOPIXEL_NANO_2427"))
    )
    (comp (ref "U$101")
      (value "NEOPIXEL_NANO_2427")
      (footprint "eagle-import:SK6805-2427")
      (libsource (lib "eagle-import") (part "NEOPIXEL_NANO_2427"))
    )
    (comp (ref "U$102")
      (value "NEOPIXEL_NANO_2427")
      (footprint "eagle-import:SK6805-2427")
      (libsource (lib "eagle-import") (part "NEOPIXEL_NANO_2427"))
    )
    (comp (ref "U$103")
      (value "NEOPIXEL_NANO_2427")
      (footprint "eagle-import:SK6805-2427")
      (libsource (lib "eagle-import") (part "NEOPIXEL_NANO_2427"))
    )
    (comp (ref "U$104")
      (value "NEOPIXEL_NANO_2427")
      (footprint "eagle-import:SK6805-2427")
      (libsource (lib "eagle-import") (part "NEOPIXEL_NANO_2427"))
    )
    (comp (ref "U$105")
      (value "NEOPIXEL_NANO_2427")
      (footprint "eagle-import:SK6805-2427")
      (libsource (lib "eagle-import") (part "NEOPIXEL_NANO_2427"))
    )
    (comp (ref "U$106")
      (value "NEOPIXEL_NANO_2427")
      (footprint "eagle-import:SK6805-2427")
      (libsource (lib "eagle-import") (part "NEOPIXEL_NANO_2427"))
    )
    (comp (ref "U$107")
      (value "NEOPIXEL_NANO_2427")
      (footprint "eagle-import:SK6805-2427")
      (libsource (lib "eagle-import") (part "NEOPIXEL_NANO_2427"))
    )
    (comp (ref "U$108")
      (value "NEOPIXEL_NANO_2427")
      (footprint "eagle-import:SK6805-2427")
      (libsource (lib "eagle-import") (part "NEOPIXEL_NANO_2427"))
    )
    (comp (ref "U$109")
      (value "NEOPIXEL_NANO_2427")
      (footprint "eagle-import:SK6805-2427")
      (libsource (lib "eagle-import") (part "NEOPIXEL_NANO_2427"))
    )
    (comp (ref "U$110")
      (value "NEOPIXEL_NANO_2427")
      (footprint "eagle-import:SK6805-2427")
      (libsource (lib "eagle-import") (part "NEOPIXEL_NANO_2427"))
    )
    (comp (ref "U$111")
      (value "NEOPIXEL_NANO_2427")
      (footprint "eagle-import:SK6805-2427")
      (libsource (lib "eagle-import") (part "NEOPIXEL_NANO_2427"))
    )
    (comp (ref "U$112")
      (value "NEOPIXEL_NANO_2427")
      (footprint "eagle-import:SK6805-2427")
      (libsource (lib "eagle-import") (part "NEOPIXEL_NANO_2427"))
    )
    (comp (ref "U$113")
      (value "NEOPIXEL_NANO_2427")
      (footprint "eagle-import:SK6805-2427")
      (libsource (lib "eagle-import") (part "NEOPIXEL_NANO_2427"))
    )
    (comp (ref "U$114")
      (value "NEOPIXEL_NANO_2427")
      (footprint "eagle-import:SK6805-2427")
      (libsource (lib "eagle-import") (part "NEOPIXEL_NANO_2427"))
    )
    (comp (ref "U$115")
      (value "NEOPIXEL_NANO_2427")
      (footprint "eagle-import:SK6805-2427")
      (libsource (lib "eagle-import") (part "NEOPIXEL_NANO_2427"))
    )
    (comp (ref "U$116")
      (value "NEOPIXEL_NANO_2427")
      (footprint "eagle-import:SK6805-2427")
      (libsource (lib "eagle-import") (part "NEOPIXEL_NANO_2427"))
    )
    (comp (ref "U$117")
      (value "NEOPIXEL_NANO_2427")
      (footprint "eagle-import:SK6805-2427")
      (libsource (lib "eagle-import") (part "NEOPIXEL_NANO_2427"))
    )
    (comp (ref "U$118")
      (value "NEOPIXEL_NANO_2427")
      (footprint "eagle-import:SK6805-2427")
      (libsource (lib "eagle-import") (part "NEOPIXEL_NANO_2427"))
    )
    (comp (ref "U$119")
      (value "NEOPIXEL_NANO_2427")
      (footprint "eagle-import:SK6805-2427")
      (libsource (lib "eagle-import") (part "NEOPIXEL_NANO_2427"))
    )
    (comp (ref "U$120")
      (value "NEOPIXEL_NANO_2427")
      (footprint "eagle-import:SK6805-2427")
      (libsource (lib "eagle-import") (part "NEOPIXEL_NANO_2427"))
    )
    (comp (ref "U$121")
      (value "NEOPIXEL_NANO_2427")
      (footprint "eagle-import:SK6805-2427")
      (libsource (lib "eagle-import") (part "NEOPIXEL_NANO_2427"))
    )
    (comp (ref "U$122")
      (value "NEOPIXEL_NANO_2427")
      (footprint "eagle-import:SK6805-2427")
      (libsource (lib "eagle-import") (part "NEOPIXEL_NANO_2427"))
    )
    (comp (ref "U$123")
      (value "NEOPIXEL_NANO_2427")
      (footprint "eagle-import:SK6805-2427")
      (libsource (lib "eagle-import") (part "NEOPIXEL_NANO_2427"))
    )
    (comp (ref "U$124")
      (value "NEOPIXEL_NANO_2427")
      (footprint "eagle-import:SK6805-2427")
      (libsource (lib "eagle-import") (part "NEOPIXEL_NANO_2427"))
    )
    (comp (ref "U$125")
      (value "NEOPIXEL_NANO_2427")
      (footprint "eagle-import:SK6805-2427")
      (libsource (lib "eagle-import") (part "NEOPIXEL_NANO_2427"))
    )
  )
  (nets
    (net (code "1") (name "/DIN") (class "Default")
      (node (ref "J1") (pin "3") (pinfunction "3_3") (pintype "passive"))
      (node (ref "R1") (pin "1") (pinfunction "1_1") (pintype "passive"))
    )
    (net (code "2") (name "/VCC") (class "Default")
      (node (ref "C1") (pin "1") (pinfunction "1_1") (pintype "passive"))
      (node (ref "C10") (pin "1") (pinfunction "1_1") (pintype "passive"))
      (node (ref "C100") (pin "1") (pinfunction "1_1") (pintype "passive"))
      (node (ref "C101") (pin "1") (pinfunction "1_1") (pintype "passive"))
      (node (ref "C102") (pin "1") (pinfunction "1_1") (pintype "passive"))
      (node (ref "C103") (pin "1") (pinfunction "1_1") (pintype "passive"))
      (node (ref "C104") (pin "1") (pinfunction "1_1") (pintype "passive"))
      (node (ref "C105") (pin "1") (pinfunction "1_1") (pintype "passive"))
      (node (ref "C106") (pin "1") (pinfunction "1_1") (pintype "passive"))
      (node (ref "C107") (pin "1") (pinfunction "1_1") (pintype "passive"))
      (node (ref "C108") (pin "1") (pinfunction "1_1") (pintype "passive"))
      (node (ref "C109") (pin "1") (pinfunction "1_1") (pintype "passive"))
      (node (ref "C11") (pin "1") (pinfunction "1_1") (pintype "passive"))
      (node (ref "C110") (pin "1") (pinfunction "1_1") (pintype "passive"))
      (node (ref "C111") (pin "1") (pinfunction "1_1") (pintype "passive"))
      (node (ref "C112") (pin "1") (pinfunction "1_1") (pintype "passive"))
      (node (ref "C113") (pin "1") (pinfunction "1_1") (pintype "passive"))
      (node (ref "C114") (pin "1") (pinfunction "1_1") (pintype "passive"))
      (node (ref "C115") (pin "1") (pinfunction "1_1") (pintype "passive"))
      (node (ref "C116") (pin "1") (pinfunction "1_1") (pintype "passive"))
      (node (ref "C117") (pin "1") (pinfunction "1_1") (pintype "passive"))
      (node (ref "C118") (pin "1") (pinfunction "1_1") (pintype "passive"))
      (node (ref "C119") (pin "1") (pinfunction "1_1") (pintype "passive"))
      (node (ref "C12") (pin "1") (pinfunction "1_1") (pintype "passive"))
      (node (ref "C120") (pin "1") (pinfunction "1_1") (pintype "passive"))
      (node (ref "C121") (pin "1") (pinfunction "1_1") (pintype "passive"))
      (node (ref "C122") (pin "1") (pinfunction "1_1") (pintype "passive"))
      (node (ref "C123") (pin "1") (pinfunction "1_1") (pintype "passive"))
      (node (ref "C124") (pin "1") (pinfunction "1_1") (pintype "passive"))
      (node (ref "C125") (pin "1") (pinfunction "1_1") (pintype "passive"))
      (node (ref "C126") (pin "1") (pinfunction "1_1") (pintype "passive"))
      (node (ref "C13") (pin "1") (pinfunction "1_1") (pintype "passive"))
      (node (ref "C14") (pin "1") (pinfunction "1_1") (pintype "passive"))
      (node (ref "C15") (pin "1") (pinfunction "1_1") (pintype "passive"))
      (node (ref "C16") (pin "1") (pinfunction "1_1") (pintype "passive"))
      (node (ref "C17") (pin "1") (pinfunction "1_1") (pintype "passive"))
      (node (ref "C18") (pin "1") (pinfunction "1_1") (pintype "passive"))
      (node (ref "C19") (pin "1") (pinfunction "1_1") (pintype "passive"))
      (node (ref "C2") (pin "+") (pinfunction "+_+") (pintype "passive"))
      (node (ref "C20") (pin "1") (pinfunction "1_1") (pintype "passive"))
      (node (ref "C21") (pin "1") (pinfunction "1_1") (pintype "passive"))
      (node (ref "C22") (pin "1") (pinfunction "1_1") (pintype "passive"))
      (node (ref "C23") (pin "1") (pinfunction "1_1") (pintype "passive"))
      (node (ref "C24") (pin "1") (pinfunction "1_1") (pintype "passive"))
      (node (ref "C25") (pin "1") (pinfunction "1_1") (pintype "passive"))
      (node (ref "C26") (pin "1") (pinfunction "1_1") (pintype "passive"))
      (node (ref "C27") (pin "1") (pinfunction "1_1") (pintype "passive"))
      (node (ref "C28") (pin "1") (pinfunction "1_1") (pintype "passive"))
      (node (ref "C29") (pin "1") (pinfunction "1_1") (pintype "passive"))
      (node (ref "C3") (pin "1") (pinfunction "1_1") (pintype "passive"))
      (node (ref "C30") (pin "1") (pinfunction "1_1") (pintype "passive"))
      (node (ref "C31") (pin "1") (pinfunction "1_1") (pintype "passive"))
      (node (ref "C32") (pin "1") (pinfunction "1_1") (pintype "passive"))
      (node (ref "C33") (pin "1") (pinfunction "1_1") (pintype "passive"))
      (node (ref "C34") (pin "1") (pinfunction "1_1") (pintype "passive"))
      (node (ref "C35") (pin "1") (pinfunction "1_1") (pintype "passive"))
      (node (ref "C36") (pin "1") (pinfunction "1_1") (pintype "passive"))
      (node (ref "C37") (pin "1") (pinfunction "1_1") (pintype "passive"))
      (node (ref "C38") (pin "1") (pinfunction "1_1") (pintype "passive"))
      (node (ref "C39") (pin "1") (pinfunction "1_1") (pintype "passive"))
      (node (ref "C4") (pin "2") (pinfunction "2_2") (pintype "passive"))
      (node (ref "C40") (pin "1") (pinfunction "1_1") (pintype "passive"))
      (node (ref "C41") (pin "1") (pinfunction "1_1") (pintype "passive"))
      (node (ref "C42") (pin "1") (pinfunction "1_1") (pintype "passive"))
      (node (ref "C43") (pin "1") (pinfunction "1_1") (pintype "passive"))
      (node (ref "C44") (pin "1") (pinfunction "1_1") (pintype "passive"))
      (node (ref "C45") (pin "1") (pinfunction "1_1") (pintype "passive"))
      (node (ref "C46") (pin "1") (pinfunction "1_1") (pintype "passive"))
      (node (ref "C47") (pin "1") (pinfunction "1_1") (pintype "passive"))
      (node (ref "C48") (pin "1") (pinfunction "1_1") (pintype "passive"))
      (node (ref "C49") (pin "1") (pinfunction "1_1") (pintype "passive"))
      (node (ref "C5") (pin "2") (pinfunction "2_2") (pintype "passive"))
      (node (ref "C50") (pin "1") (pinfunction "1_1") (pintype "passive"))
      (node (ref "C51") (pin "1") (pinfunction "1_1") (pintype "passive"))
      (node (ref "C52") (pin "1") (pinfunction "1_1") (pintype "passive"))
      (node (ref "C53") (pin "1") (pinfunction "1_1") (pintype "passive"))
      (node (ref "C54") (pin "1") (pinfunction "1_1") (pintype "passive"))
      (node (ref "C55") (pin "1") (pinfunction "1_1") (pintype "passive"))
      (node (ref "C56") (pin "1") (pinfunction "1_1") (pintype "passive"))
      (node (ref "C57") (pin "1") (pinfunction "1_1") (pintype "passive"))
      (node (ref "C58") (pin "1") (pinfunction "1_1") (pintype "passive"))
      (node (ref "C59") (pin "1") (pinfunction "1_1") (pintype "passive"))
      (node (ref "C6") (pin "2") (pinfunction "2_2") (pintype "passive"))
      (node (ref "C60") (pin "1") (pinfunction "1_1") (pintype "passive"))
      (node (ref "C61") (pin "1") (pinfunction "1_1") (pintype "passive"))
      (node (ref "C62") (pin "1") (pinfunction "1_1") (pintype "passive"))
      (node (ref "C63") (pin "1") (pinfunction "1_1") (pintype "passive"))
      (node (ref "C64") (pin "1") (pinfunction "1_1") (pintype "passive"))
      (node (ref "C65") (pin "1") (pinfunction "1_1") (pintype "passive"))
      (node (ref "C66") (pin "1") (pinfunction "1_1") (pintype "passive"))
      (node (ref "C67") (pin "1") (pinfunction "1_1") (pintype "passive"))
      (node (ref "C68") (pin "1") (pinfunction "1_1") (pintype "passive"))
      (node (ref "C69") (pin "1") (pinfunction "1_1") (pintype "passive"))
      (node (ref "C7") (pin "2") (pinfunction "2_2") (pintype "passive"))
      (node (ref "C70") (pin "1") (pinfunction "1_1") (pintype "passive"))
      (node (ref "C71") (pin "1") (pinfunction "1_1") (pintype "passive"))
      (node (ref "C72") (pin "1") (pinfunction "1_1") (pintype "passive"))
      (node (ref "C73") (pin "1") (pinfunction "1_1") (pintype "passive"))
      (node (ref "C74") (pin "1") (pinfunction "1_1") (pintype "passive"))
      (node (ref "C75") (pin "1") (pinfunction "1_1") (pintype "passive"))
      (node (ref "C76") (pin "1") (pinfunction "1_1") (pintype "passive"))
      (node (ref "C77") (pin "1") (pinfunction "1_1") (pintype "passive"))
      (node (ref "C78") (pin "1") (pinfunction "1_1") (pintype "passive"))
      (node (ref "C79") (pin "1") (pinfunction "1_1") (pintype "passive"))
      (node (ref "C8") (pin "1") (pinfunction "1_1") (pintype "passive"))
      (node (ref "C80") (pin "1") (pinfunction "1_1") (pintype "passive"))
      (node (ref "C81") (pin "1") (pinfunction "1_1") (pintype "passive"))
      (node (ref "C82") (pin "1") (pinfunction "1_1") (pintype "passive"))
      (node (ref "C83") (pin "1") (pinfunction "1_1") (pintype "passive"))
      (node (ref "C84") (pin "1") (pinfunction "1_1") (pintype "passive"))
      (node (ref "C85") (pin "1") (pinfunction "1_1") (pintype "passive"))
      (node (ref "C86") (pin "1") (pinfunction "1_1") (pintype "passive"))
      (node (ref "C87") (pin "1") (pinfunction "1_1") (pintype "passive"))
      (node (ref "C88") (pin "1") (pinfunction "1_1") (pintype "passive"))
      (node (ref "C89") (pin "1") (pinfunction "1_1") (pintype "passive"))
      (node (ref "C9") (pin "1") (pinfunction "1_1") (pintype "passive"))
      (node (ref "C90") (pin "1") (pinfunction "1_1") (pintype "passive"))
      (node (ref "C91") (pin "1") (pinfunction "1_1") (pintype "passive"))
      (node (ref "C92") (pin "1") (pinfunction "1_1") (pintype "passive"))
      (node (ref "C93") (pin "1") (pinfunction "1_1") (pintype "passive"))
      (node (ref "C94") (pin "1") (pinfunction "1_1") (pintype "passive"))
      (node (ref "C95") (pin "1") (pinfunction "1_1") (pintype "passive"))
      (node (ref "C96") (pin "1") (pinfunction "1_1") (pintype "passive"))
      (node (ref "C97") (pin "1") (pinfunction "1_1") (pintype "passive"))
      (node (ref "C98") (pin "1") (pinfunction "1_1") (pintype "passive"))
      (node (ref "C99") (pin "1") (pinfunction "1_1") (pintype "passive"))
      (node (ref "J1") (pin "1") (pinfunction "1_1") (pintype "passive"))
      (node (ref "U$1") (pin "VCC") (pinfunction "VDD_VCC") (pintype "bidirectional"))
      (node (ref "U$10") (pin "VCC") (pinfunction "VDD_VCC") (pintype "bidirectional"))
      (node (ref "U$100") (pin "VCC") (pinfunction "VDD_VCC") (pintype "bidirectional"))
      (node (ref "U$101") (pin "VCC") (pinfunction "VDD_VCC") (pintype "bidirectional"))
      (node (ref "U$102") (pin "VCC") (pinfunction "VDD_VCC") (pintype "bidirectional"))
      (node (ref "U$103") (pin "VCC") (pinfunction "VDD_VCC") (pintype "bidirectional"))
      (node (ref "U$104") (pin "VCC") (pinfunction "VDD_VCC") (pintype "bidirectional"))
      (node (ref "U$105") (pin "VCC") (pinfunction "VDD_VCC") (pintype "bidirectional"))
      (node (ref "U$106") (pin "VCC") (pinfunction "VDD_VCC") (pintype "bidirectional"))
      (node (ref "U$107") (pin "VCC") (pinfunction "VDD_VCC") (pintype "bidirectional"))
      (node (ref "U$108") (pin "VCC") (pinfunction "VDD_VCC") (pintype "bidirectional"))
      (node (ref "U$109") (pin "VCC") (pinfunction "VDD_VCC") (pintype "bidirectional"))
      (node (ref "U$11") (pin "VCC") (pinfunction "VDD_VCC") (pintype "bidirectional"))
      (node (ref "U$110") (pin "VCC") (pinfunction "VDD_VCC") (pintype "bidirectional"))
      (node (ref "U$111") (pin "VCC") (pinfunction "VDD_VCC") (pintype "bidirectional"))
      (node (ref "U$112") (pin "VCC") (pinfunction "VDD_VCC") (pintype "bidirectional"))
      (node (ref "U$113") (pin "VCC") (pinfunction "VDD_VCC") (pintype "bidirectional"))
      (node (ref "U$114") (pin "VCC") (pinfunction "VDD_VCC") (pintype "bidirectional"))
      (node (ref "U$115") (pin "VCC") (pinfunction "VDD_VCC") (pintype "bidirectional"))
      (node (ref "U$116") (pin "VCC") (pinfunction "VDD_VCC") (pintype "bidirectional"))
      (node (ref "U$117") (pin "VCC") (pinfunction "VDD_VCC") (pintype "bidirectional"))
      (node (ref "U$118") (pin "VCC") (pinfunction "VDD_VCC") (pintype "bidirectional"))
      (node (ref "U$119") (pin "VCC") (pinfunction "VDD_VCC") (pintype "bidirectional"))
      (node (ref "U$12") (pin "VCC") (pinfunction "VDD_VCC") (pintype "bidirectional"))
      (node (ref "U$120") (pin "VCC") (pinfunction "VDD_VCC") (pintype "bidirectional"))
      (node (ref "U$121") (pin "VCC") (pinfunction "VDD_VCC") (pintype "bidirectional"))
      (node (ref "U$122") (pin "VCC") (pinfunction "VDD_VCC") (pintype "bidirectional"))
      (node (ref "U$123") (pin "VCC") (pinfunction "VDD_VCC") (pintype "bidirectional"))
      (node (ref "U$124") (pin "VCC") (pinfunction "VDD_VCC") (pintype "bidirectional"))
      (node (ref "U$125") (pin "VCC") (pinfunction "VDD_VCC") (pintype "bidirectional"))
      (node (ref "U$13") (pin "VCC") (pinfunction "VDD_VCC") (pintype "bidirectional"))
      (node (ref "U$14") (pin "VCC") (pinfunction "VDD_VCC") (pintype "bidirectional"))
      (node (ref "U$15") (pin "VCC") (pinfunction "VDD_VCC") (pintype "bidirectional"))
      (node (ref "U$16") (pin "VCC") (pinfunction "VDD_VCC") (pintype "bidirectional"))
      (node (ref "U$17") (pin "VCC") (pinfunction "VDD_VCC") (pintype "bidirectional"))
      (node (ref "U$18") (pin "VCC") (pinfunction "VDD_VCC") (pintype "bidirectional"))
      (node (ref "U$19") (pin "VCC") (pinfunction "VDD_VCC") (pintype "bidirectional"))
      (node (ref "U$2") (pin "VCC") (pinfunction "VDD_VCC") (pintype "bidirectional"))
      (node (ref "U$20") (pin "VCC") (pinfunction "VDD_VCC") (pintype "bidirectional"))
      (node (ref "U$21") (pin "VCC") (pinfunction "VDD_VCC") (pintype "bidirectional"))
      (node (ref "U$22") (pin "VCC") (pinfunction "VDD_VCC") (pintype "bidirectional"))
      (node (ref "U$23") (pin "VCC") (pinfunction "VDD_VCC") (pintype "bidirectional"))
      (node (ref "U$24") (pin "VCC") (pinfunction "VDD_VCC") (pintype "bidirectional"))
      (node (ref "U$25") (pin "VCC") (pinfunction "VDD_VCC") (pintype "bidirectional"))
      (node (ref "U$26") (pin "VCC") (pinfunction "VDD_VCC") (pintype "bidirectional"))
      (node (ref "U$27") (pin "VCC") (pinfunction "VDD_VCC") (pintype "bidirectional"))
      (node (ref "U$28") (pin "VCC") (pinfunction "VDD_VCC") (pintype "bidirectional"))
      (node (ref "U$29") (pin "VCC") (pinfunction "VDD_VCC") (pintype "bidirectional"))
      (node (ref "U$3") (pin "VCC") (pinfunction "VDD_VCC") (pintype "bidirectional"))
      (node (ref "U$30") (pin "VCC") (pinfunction "VDD_VCC") (pintype "bidirectional"))
      (node (ref "U$31") (pin "VCC") (pinfunction "VDD_VCC") (pintype "bidirectional"))
      (node (ref "U$32") (pin "VCC") (pinfunction "VDD_VCC") (pintype "bidirectional"))
      (node (ref "U$33") (pin "VCC") (pinfunction "VDD_VCC") (pintype "bidirectional"))
      (node (ref "U$34") (pin "VCC") (pinfunction "VDD_VCC") (pintype "bidirectional"))
      (node (ref "U$35") (pin "VCC") (pinfunction "VDD_VCC") (pintype "bidirectional"))
      (node (ref "U$36") (pin "VCC") (pinfunction "VDD_VCC") (pintype "bidirectional"))
      (node (ref "U$37") (pin "VCC") (pinfunction "VDD_VCC") (pintype "bidirectional"))
      (node (ref "U$38") (pin "VCC") (pinfunction "VDD_VCC") (pintype "bidirectional"))
      (node (ref "U$39") (pin "VCC") (pinfunction "VDD_VCC") (pintype "bidirectional"))
      (node (ref "U$4") (pin "VCC") (pinfunction "VDD_VCC") (pintype "bidirectional"))
      (node (ref "U$40") (pin "VCC") (pinfunction "VDD_VCC") (pintype "bidirectional"))
      (node (ref "U$41") (pin "VCC") (pinfunction "VDD_VCC") (pintype "bidirectional"))
      (node (ref "U$42") (pin "VCC") (pinfunction "VDD_VCC") (pintype "bidirectional"))
      (node (ref "U$43") (pin "VCC") (pinfunction "VDD_VCC") (pintype "bidirectional"))
      (node (ref "U$44") (pin "VCC") (pinfunction "VDD_VCC") (pintype "bidirectional"))
      (node (ref "U$45") (pin "VCC") (pinfunction "VDD_VCC") (pintype "bidirectional"))
      (node (ref "U$46") (pin "VCC") (pinfunction "VDD_VCC") (pintype "bidirectional"))
      (node (ref "U$47") (pin "VCC") (pinfunction "VDD_VCC") (pintype "bidirectional"))
      (node (ref "U$48") (pin "VCC") (pinfunction "VDD_VCC") (pintype "bidirectional"))
      (node (ref "U$49") (pin "VCC") (pinfunction "VDD_VCC") (pintype "bidirectional"))
      (node (ref "U$5") (pin "VCC") (pinfunction "VDD_VCC") (pintype "bidirectional"))
      (node (ref "U$50") (pin "VCC") (pinfunction "VDD_VCC") (pintype "bidirectional"))
      (node (ref "U$51") (pin "VCC") (pinfunction "VDD_VCC") (pintype "bidirectional"))
      (node (ref "U$52") (pin "VCC") (pinfunction "VDD_VCC") (pintype "bidirectional"))
      (node (ref "U$53") (pin "VCC") (pinfunction "VDD_VCC") (pintype "bidirectional"))
      (node (ref "U$54") (pin "VCC") (pinfunction "VDD_VCC") (pintype "bidirectional"))
      (node (ref "U$55") (pin "VCC") (pinfunction "VDD_VCC") (pintype "bidirectional"))
      (node (ref "U$56") (pin "VCC") (pinfunction "VDD_VCC") (pintype "bidirectional"))
      (node (ref "U$57") (pin "VCC") (pinfunction "VDD_VCC") (pintype "bidirectional"))
      (node (ref "U$58") (pin "VCC") (pinfunction "VDD_VCC") (pintype "bidirectional"))
      (node (ref "U$59") (pin "VCC") (pinfunction "VDD_VCC") (pintype "bidirectional"))
      (node (ref "U$6") (pin "VCC") (pinfunction "VDD_VCC") (pintype "bidirectional"))
      (node (ref "U$60") (pin "VCC") (pinfunction "VDD_VCC") (pintype "bidirectional"))
      (node (ref "U$61") (pin "VCC") (pinfunction "VDD_VCC") (pintype "bidirectional"))
      (node (ref "U$62") (pin "VCC") (pinfunction "VDD_VCC") (pintype "bidirectional"))
      (node (ref "U$63") (pin "VCC") (pinfunction "VDD_VCC") (pintype "bidirectional"))
      (node (ref "U$64") (pin "VCC") (pinfunction "VDD_VCC") (pintype "bidirectional"))
      (node (ref "U$65") (pin "VCC") (pinfunction "VDD_VCC") (pintype "bidirectional"))
      (node (ref "U$66") (pin "VCC") (pinfunction "VDD_VCC") (pintype "bidirectional"))
      (node (ref "U$67") (pin "VCC") (pinfunction "VDD_VCC") (pintype "bidirectional"))
      (node (ref "U$68") (pin "VCC") (pinfunction "VDD_VCC") (pintype "bidirectional"))
      (node (ref "U$69") (pin "VCC") (pinfunction "VDD_VCC") (pintype "bidirectional"))
      (node (ref "U$7") (pin "VCC") (pinfunction "VDD_VCC") (pintype "bidirectional"))
      (node (ref "U$70") (pin "VCC") (pinfunction "VDD_VCC") (pintype "bidirectional"))
      (node (ref "U$71") (pin "VCC") (pinfunction "VDD_VCC") (pintype "bidirectional"))
      (node (ref "U$72") (pin "VCC") (pinfunction "VDD_VCC") (pintype "bidirectional"))
      (node (ref "U$73") (pin "VCC") (pinfunction "VDD_VCC") (pintype "bidirectional"))
      (node (ref "U$74") (pin "VCC") (pinfunction "VDD_VCC") (pintype "bidirectional"))
      (node (ref "U$75") (pin "VCC") (pinfunction "VDD_VCC") (pintype "bidirectional"))
      (node (ref "U$76") (pin "VCC") (pinfunction "VDD_VCC") (pintype "bidirectional"))
      (node (ref "U$77") (pin "VCC") (pinfunction "VDD_VCC") (pintype "bidirectional"))
      (node (ref "U$78") (pin "VCC") (pinfunction "VDD_VCC") (pintype "bidirectional"))
      (node (ref "U$79") (pin "VCC") (pinfunction "VDD_VCC") (pintype "bidirectional"))
      (node (ref "U$8") (pin "VCC") (pinfunction "VDD_VCC") (pintype "bidirectional"))
      (node (ref "U$80") (pin "VCC") (pinfunction "VDD_VCC") (pintype "bidirectional"))
      (node (ref "U$81") (pin "VCC") (pinfunction "VDD_VCC") (pintype "bidirectional"))
      (node (ref "U$82") (pin "VCC") (pinfunction "VDD_VCC") (pintype "bidirectional"))
      (node (ref "U$83") (pin "VCC") (pinfunction "VDD_VCC") (pintype "bidirectional"))
      (node (ref "U$84") (pin "VCC") (pinfunction "VDD_VCC") (pintype "bidirectional"))
      (node (ref "U$85") (pin "VCC") (pinfunction "VDD_VCC") (pintype "bidirectional"))
      (node (ref "U$86") (pin "VCC") (pinfunction "VDD_VCC") (pintype "bidirectional"))
      (node (ref "U$87") (pin "VCC") (pinfunction "VDD_VCC") (pintype "bidirectional"))
      (node (ref "U$88") (pin "VCC") (pinfunction "VDD_VCC") (pintype "bidirectional"))
      (node (ref "U$89") (pin "VCC") (pinfunction "VDD_VCC") (pintype "bidirectional"))
      (node (ref "U$9") (pin "VCC") (pinfunction "VDD_VCC") (pintype "bidirectional"))
      (node (ref "U$90") (pin "VCC") (pinfunction "VDD_VCC") (pintype "bidirectional"))
      (node (ref "U$91") (pin "VCC") (pinfunction "VDD_VCC") (pintype "bidirectional"))
      (node (ref "U$92") (pin "VCC") (pinfunction "VDD_VCC") (pintype "bidirectional"))
      (node (ref "U$93") (pin "VCC") (pinfunction "VDD_VCC") (pintype "bidirectional"))
      (node (ref "U$94") (pin "VCC") (pinfunction "VDD_VCC") (pintype "bidirectional"))
      (node (ref "U$95") (pin "VCC") (pinfunction "VDD_VCC") (pintype "bidirectional"))
      (node (ref "U$96") (pin "VCC") (pinfunction "VDD_VCC") (pintype "bidirectional"))
      (node (ref "U$97") (pin "VCC") (pinfunction "VDD_VCC") (pintype "bidirectional"))
      (node (ref "U$98") (pin "VCC") (pinfunction "VDD_VCC") (pintype "bidirectional"))
      (node (ref "U$99") (pin "VCC") (pinfunction "VDD_VCC") (pintype "bidirectional"))
    )
    (net (code "3") (name "GND") (class "Default")
      (node (ref "C1") (pin "2") (pinfunction "2_2") (pintype "passive"))
      (node (ref "C10") (pin "2") (pinfunction "2_2") (pintype "passive"))
      (node (ref "C100") (pin "2") (pinfunction "2_2") (pintype "passive"))
      (node (ref "C101") (pin "2") (pinfunction "2_2") (pintype "passive"))
      (node (ref "C102") (pin "2") (pinfunction "2_2") (pintype "passive"))
      (node (ref "C103") (pin "2") (pinfunction "2_2") (pintype "passive"))
      (node (ref "C104") (pin "2") (pinfunction "2_2") (pintype "passive"))
      (node (ref "C105") (pin "2") (pinfunction "2_2") (pintype "passive"))
      (node (ref "C106") (pin "2") (pinfunction "2_2") (pintype "passive"))
      (node (ref "C107") (pin "2") (pinfunction "2_2") (pintype "passive"))
      (node (ref "C108") (pin "2") (pinfunction "2_2") (pintype "passive"))
      (node (ref "C109") (pin "2") (pinfunction "2_2") (pintype "passive"))
      (node (ref "C11") (pin "2") (pinfunction "2_2") (pintype "passive"))
      (node (ref "C110") (pin "2") (pinfunction "2_2") (pintype "passive"))
      (node (ref "C111") (pin "2") (pinfunction "2_2") (pintype "passive"))
      (node (ref "C112") (pin "2") (pinfunction "2_2") (pintype "passive"))
      (node (ref "C113") (pin "2") (pinfunction "2_2") (pintype "passive"))
      (node (ref "C114") (pin "2") (pinfunction "2_2") (pintype "passive"))
      (node (ref "C115") (pin "2") (pinfunction "2_2") (pintype "passive"))
      (node (ref "C116") (pin "2") (pinfunction "2_2") (pintype "passive"))
      (node (ref "C117") (pin "2") (pinfunction "2_2") (pintype "passive"))
      (node (ref "C118") (pin "2") (pinfunction "2_2") (pintype "passive"))
      (node (ref "C119") (pin "2") (pinfunction "2_2") (pintype "passive"))
      (node (ref "C12") (pin "2") (pinfunction "2_2") (pintype "passive"))
      (node (ref "C120") (pin "2") (pinfunction "2_2") (pintype "passive"))
      (node (ref "C121") (pin "2") (pinfunction "2_2") (pintype "passive"))
      (node (ref "C122") (pin "2") (pinfunction "2_2") (pintype "passive"))
      (node (ref "C123") (pin "2") (pinfunction "2_2") (pintype "passive"))
      (node (ref "C124") (pin "2") (pinfunction "2_2") (pintype "passive"))
      (node (ref "C125") (pin "2") (pinfunction "2_2") (pintype "passive"))
      (node (ref "C126") (pin "2") (pinfunction "2_2") (pintype "passive"))
      (node (ref "C13") (pin "2") (pinfunction "2_2") (pintype "passive"))
      (node (ref "C14") (pin "2") (pinfunction "2_2") (pintype "passive"))
      (node (ref "C15") (pin "2") (pinfunction "2_2") (pintype "passive"))
      (node (ref "C16") (pin "2") (pinfunction "2_2") (pintype "passive"))
      (node (ref "C17") (pin "2") (pinfunction "2_2") (pintype "passive"))
      (node (ref "C18") (pin "2") (pinfunction "2_2") (pintype "passive"))
      (node (ref "C19") (pin "2") (pinfunction "2_2") (pintype "passive"))
      (node (ref "C2") (pin "-") (pinfunction "-_-") (pintype "passive"))
      (node (ref "C20") (pin "2") (pinfunction "2_2") (pintype "passive"))
      (node (ref "C21") (pin "2") (pinfunction "2_2") (pintype "passive"))
      (node (ref "C22") (pin "2") (pinfunction "2_2") (pintype "passive"))
      (node (ref "C23") (pin "2") (pinfunction "2_2") (pintype "passive"))
      (node (ref "C24") (pin "2") (pinfunction "2_2") (pintype "passive"))
      (node (ref "C25") (pin "2") (pinfunction "2_2") (pintype "passive"))
      (node (ref "C26") (pin "2") (pinfunction "2_2") (pintype "passive"))
      (node (ref "C27") (pin "2") (pinfunction "2_2") (pintype "passive"))
      (node (ref "C28") (pin "2") (pinfunction "2_2") (pintype "passive"))
      (node (ref "C29") (pin "2") (pinfunction "2_2") (pintype "passive"))
      (node (ref "C3") (pin "2") (pinfunction "2_2") (pintype "passive"))
      (node (ref "C30") (pin "2") (pinfunction "2_2") (pintype "passive"))
      (node (ref "C31") (pin "2") (pinfunction "2_2") (pintype "passive"))
      (node (ref "C32") (pin "2") (pinfunction "2_2") (pintype "passive"))
      (node (ref "C33") (pin "2") (pinfunction "2_2") (pintype "passive"))
      (node (ref "C34") (pin "2") (pinfunction "2_2") (pintype "passive"))
      (node (ref "C35") (pin "2") (pinfunction "2_2") (pintype "passive"))
      (node (ref "C36") (pin "2") (pinfunction "2_2") (pintype "passive"))
      (node (ref "C37") (pin "2") (pinfunction "2_2") (pintype "passive"))
      (node (ref "C38") (pin "2") (pinfunction "2_2") (pintype "passive"))
      (node (ref "C39") (pin "2") (pinfunction "2_2") (pintype "passive"))
      (node (ref "C4") (pin "1") (pinfunction "1_1") (pintype "passive"))
      (node (ref "C40") (pin "2") (pinfunction "2_2") (pintype "passive"))
      (node (ref "C41") (pin "2") (pinfunction "2_2") (pintype "passive"))
      (node (ref "C42") (pin "2") (pinfunction "2_2") (pintype "passive"))
      (node (ref "C43") (pin "2") (pinfunction "2_2") (pintype "passive"))
      (node (ref "C44") (pin "2") (pinfunction "2_2") (pintype "passive"))
      (node (ref "C45") (pin "2") (pinfunction "2_2") (pintype "passive"))
      (node (ref "C46") (pin "2") (pinfunction "2_2") (pintype "passive"))
      (node (ref "C47") (pin "2") (pinfunction "2_2") (pintype "passive"))
      (node (ref "C48") (pin "2") (pinfunction "2_2") (pintype "passive"))
      (node (ref "C49") (pin "2") (pinfunction "2_2") (pintype "passive"))
      (node (ref "C5") (pin "1") (pinfunction "1_1") (pintype "passive"))
      (node (ref "C50") (pin "2") (pinfunction "2_2") (pintype "passive"))
      (node (ref "C51") (pin "2") (pinfunction "2_2") (pintype "passive"))
      (node (ref "C52") (pin "2") (pinfunction "2_2") (pintype "passive"))
      (node (ref "C53") (pin "2") (pinfunction "2_2") (pintype "passive"))
      (node (ref "C54") (pin "2") (pinfunction "2_2") (pintype "passive"))
      (node (ref "C55") (pin "2") (pinfunction "2_2") (pintype "passive"))
      (node (ref "C56") (pin "2") (pinfunction "2_2") (pintype "passive"))
      (node (ref "C57") (pin "2") (pinfunction "2_2") (pintype "passive"))
      (node (ref "C58") (pin "2") (pinfunction "2_2") (pintype "passive"))
      (node (ref "C59") (pin "2") (pinfunction "2_2") (pintype "passive"))
      (node (ref "C6") (pin "1") (pinfunction "1_1") (pintype "passive"))
      (node (ref "C60") (pin "2") (pinfunction "2_2") (pintype "passive"))
      (node (ref "C61") (pin "2") (pinfunction "2_2") (pintype "passive"))
      (node (ref "C62") (pin "2") (pinfunction "2_2") (pintype "passive"))
      (node (ref "C63") (pin "2") (pinfunction "2_2") (pintype "passive"))
      (node (ref "C64") (pin "2") (pinfunction "2_2") (pintype "passive"))
      (node (ref "C65") (pin "2") (pinfunction "2_2") (pintype "passive"))
      (node (ref "C66") (pin "2") (pinfunction "2_2") (pintype "passive"))
      (node (ref "C67") (pin "2") (pinfunction "2_2") (pintype "passive"))
      (node (ref "C68") (pin "2") (pinfunction "2_2") (pintype "passive"))
      (node (ref "C69") (pin "2") (pinfunction "2_2") (pintype "passive"))
      (node (ref "C7") (pin "1") (pinfunction "1_1") (pintype "passive"))
      (node (ref "C70") (pin "2") (pinfunction "2_2") (pintype "passive"))
      (node (ref "C71") (pin "2") (pinfunction "2_2") (pintype "passive"))
      (node (ref "C72") (pin "2") (pinfunction "2_2") (pintype "passive"))
      (node (ref "C73") (pin "2") (pinfunction "2_2") (pintype "passive"))
      (node (ref "C74") (pin "2") (pinfunction "2_2") (pintype "passive"))
      (node (ref "C75") (pin "2") (pinfunction "2_2") (pintype "passive"))
      (node (ref "C76") (pin "2") (pinfunction "2_2") (pintype "passive"))
      (node (ref "C77") (pin "2") (pinfunction "2_2") (pintype "passive"))
      (node (ref "C78") (pin "2") (pinfunction "2_2") (pintype "passive"))
      (node (ref "C79") (pin "2") (pinfunction "2_2") (pintype "passive"))
      (node (ref "C8") (pin "2") (pinfunction "2_2") (pintype "passive"))
      (node (ref "C80") (pin "2") (pinfunction "2_2") (pintype "passive"))
      (node (ref "C81") (pin "2") (pinfunction "2_2") (pintype "passive"))
      (node (ref "C82") (pin "2") (pinfunction "2_2") (pintype "passive"))
      (node (ref "C83") (pin "2") (pinfunction "2_2") (pintype "passive"))
      (node (ref "C84") (pin "2") (pinfunction "2_2") (pintype "passive"))
      (node (ref "C85") (pin "2") (pinfunction "2_2") (pintype "passive"))
      (node (ref "C86") (pin "2") (pinfunction "2_2") (pintype "passive"))
      (node (ref "C87") (pin "2") (pinfunction "2_2") (pintype "passive"))
      (node (ref "C88") (pin "2") (pinfunction "2_2") (pintype "passive"))
      (node (ref "C89") (pin "2") (pinfunction "2_2") (pintype "passive"))
      (node (ref "C9") (pin "2") (pinfunction "2_2") (pintype "passive"))
      (node (ref "C90") (pin "2") (pinfunction "2_2") (pintype "passive"))
      (node (ref "C91") (pin "2") (pinfunction "2_2") (pintype "passive"))
      (node (ref "C92") (pin "2") (pinfunction "2_2") (pintype "passive"))
      (node (ref "C93") (pin "2") (pinfunction "2_2") (pintype "passive"))
      (node (ref "C94") (pin "2") (pinfunction "2_2") (pintype "passive"))
      (node (ref "C95") (pin "2") (pinfunction "2_2") (pintype "passive"))
      (node (ref "C96") (pin "2") (pinfunction "2_2") (pintype "passive"))
      (node (ref "C97") (pin "2") (pinfunction "2_2") (pintype "passive"))
      (node (ref "C98") (pin "2") (pinfunction "2_2") (pintype "passive"))
      (node (ref "C99") (pin "2") (pinfunction "2_2") (pintype "passive"))
      (node (ref "J1") (pin "2") (pinfunction "2_2") (pintype "passive"))
      (node (ref "U$1") (pin "GND") (pinfunction "VSS_GND") (pintype "bidirectional"))
      (node (ref "U$10") (pin "GND") (pinfunction "VSS_GND") (pintype "bidirectional"))
      (node (ref "U$100") (pin "GND") (pinfunction "VSS_GND") (pintype "bidirectional"))
      (node (ref "U$101") (pin "GND") (pinfunction "VSS_GND") (pintype "bidirectional"))
      (node (ref "U$102") (pin "GND") (pinfunction "VSS_GND") (pintype "bidirectional"))
      (node (ref "U$103") (pin "GND") (pinfunction "VSS_GND") (pintype "bidirectional"))
      (node (ref "U$104") (pin "GND") (pinfunction "VSS_GND") (pintype "bidirectional"))
      (node (ref "U$105") (pin "GND") (pinfunction "VSS_GND") (pintype "bidirectional"))
      (node (ref "U$106") (pin "GND") (pinfunction "VSS_GND") (pintype "bidirectional"))
      (node (ref "U$107") (pin "GND") (pinfunction "VSS_GND") (pintype "bidirectional"))
      (node (ref "U$108") (pin "GND") (pinfunction "VSS_GND") (pintype "bidirectional"))
      (node (ref "U$109") (pin "GND") (pinfunction "VSS_GND") (pintype "bidirectional"))
      (node (ref "U$11") (pin "GND") (pinfunction "VSS_GND") (pintype "bidirectional"))
      (node (ref "U$110") (pin "GND") (pinfunction "VSS_GND") (pintype "bidirectional"))
      (node (ref "U$111") (pin "GND") (pinfunction "VSS_GND") (pintype "bidirectional"))
      (node (ref "U$112") (pin "GND") (pinfunction "VSS_GND") (pintype "bidirectional"))
      (node (ref "U$113") (pin "GND") (pinfunction "VSS_GND") (pintype "bidirectional"))
      (node (ref "U$114") (pin "GND") (pinfunction "VSS_GND") (pintype "bidirectional"))
      (node (ref "U$115") (pin "GND") (pinfunction "VSS_GND") (pintype "bidirectional"))
      (node (ref "U$116") (pin "GND") (pinfunction "VSS_GND") (pintype "bidirectional"))
      (node (ref "U$117") (pin "GND") (pinfunction "VSS_GND") (pintype "bidirectional"))
      (node (ref "U$118") (pin "GND") (pinfunction "VSS_GND") (pintype "bidirectional"))
      (node (ref "U$119") (pin "GND") (pinfunction "VSS_GND") (pintype "bidirectional"))
      (node (ref "U$12") (pin "GND") (pinfunction "VSS_GND") (pintype "bidirectional"))
      (node (ref "U$120") (pin "GND") (pinfunction "VSS_GND") (pintype "bidirectional"))
      (node (ref "U$121") (pin "GND") (pinfunction "VSS_GND") (pintype "bidirectional"))
      (node (ref "U$122") (pin "GND") (pinfunction "VSS_GND") (pintype "bidirectional"))
      (node (ref "U$123") (pin "GND") (pinfunction "VSS_GND") (pintype "bidirectional"))
      (node (ref "U$124") (pin "GND") (pinfunction "VSS_GND") (pintype "bidirectional"))
      (node (ref "U$125") (pin "GND") (pinfunction "VSS_GND") (pintype "bidirectional"))
      (node (ref "U$13") (pin "GND") (pinfunction "VSS_GND") (pintype "bidirectional"))
      (node (ref "U$14") (pin "GND") (pinfunction "VSS_GND") (pintype "bidirectional"))
      (node (ref "U$15") (pin "GND") (pinfunction "VSS_GND") (pintype "bidirectional"))
      (node (ref "U$16") (pin "GND") (pinfunction "VSS_GND") (pintype "bidirectional"))
      (node (ref "U$17") (pin "GND") (pinfunction "VSS_GND") (pintype "bidirectional"))
      (node (ref "U$18") (pin "GND") (pinfunction "VSS_GND") (pintype "bidirectional"))
      (node (ref "U$19") (pin "GND") (pinfunction "VSS_GND") (pintype "bidirectional"))
      (node (ref "U$2") (pin "GND") (pinfunction "VSS_GND") (pintype "bidirectional"))
      (node (ref "U$20") (pin "GND") (pinfunction "VSS_GND") (pintype "bidirectional"))
      (node (ref "U$21") (pin "GND") (pinfunction "VSS_GND") (pintype "bidirectional"))
      (node (ref "U$22") (pin "GND") (pinfunction "VSS_GND") (pintype "bidirectional"))
      (node (ref "U$23") (pin "GND") (pinfunction "VSS_GND") (pintype "bidirectional"))
      (node (ref "U$24") (pin "GND") (pinfunction "VSS_GND") (pintype "bidirectional"))
      (node (ref "U$25") (pin "GND") (pinfunction "VSS_GND") (pintype "bidirectional"))
      (node (ref "U$26") (pin "GND") (pinfunction "VSS_GND") (pintype "bidirectional"))
      (node (ref "U$27") (pin "GND") (pinfunction "VSS_GND") (pintype "bidirectional"))
      (node (ref "U$28") (pin "GND") (pinfunction "VSS_GND") (pintype "bidirectional"))
      (node (ref "U$29") (pin "GND") (pinfunction "VSS_GND") (pintype "bidirectional"))
      (node (ref "U$3") (pin "GND") (pinfunction "VSS_GND") (pintype "bidirectional"))
      (node (ref "U$30") (pin "GND") (pinfunction "VSS_GND") (pintype "bidirectional"))
      (node (ref "U$31") (pin "GND") (pinfunction "VSS_GND") (pintype "bidirectional"))
      (node (ref "U$32") (pin "GND") (pinfunction "VSS_GND") (pintype "bidirectional"))
      (node (ref "U$33") (pin "GND") (pinfunction "VSS_GND") (pintype "bidirectional"))
      (node (ref "U$34") (pin "GND") (pinfunction "VSS_GND") (pintype "bidirectional"))
      (node (ref "U$35") (pin "GND") (pinfunction "VSS_GND") (pintype "bidirectional"))
      (node (ref "U$36") (pin "GND") (pinfunction "VSS_GND") (pintype "bidirectional"))
      (node (ref "U$37") (pin "GND") (pinfunction "VSS_GND") (pintype "bidirectional"))
      (node (ref "U$38") (pin "GND") (pinfunction "VSS_GND") (pintype "bidirectional"))
      (node (ref "U$39") (pin "GND") (pinfunction "VSS_GND") (pintype "bidirectional"))
      (node (ref "U$4") (pin "GND") (pinfunction "VSS_GND") (pintype "bidirectional"))
      (node (ref "U$40") (pin "GND") (pinfunction "VSS_GND") (pintype "bidirectional"))
      (node (ref "U$41") (pin "GND") (pinfunction "VSS_GND") (pintype "bidirectional"))
      (node (ref "U$42") (pin "GND") (pinfunction "VSS_GND") (pintype "bidirectional"))
      (node (ref "U$43") (pin "GND") (pinfunction "VSS_GND") (pintype "bidirectional"))
      (node (ref "U$44") (pin "GND") (pinfunction "VSS_GND") (pintype "bidirectional"))
      (node (ref "U$45") (pin "GND") (pinfunction "VSS_GND") (pintype "bidirectional"))
      (node (ref "U$46") (pin "GND") (pinfunction "VSS_GND") (pintype "bidirectional"))
      (node (ref "U$47") (pin "GND") (pinfunction "VSS_GND") (pintype "bidirectional"))
      (node (ref "U$48") (pin "GND") (pinfunction "VSS_GND") (pintype "bidirectional"))
      (node (ref "U$49") (pin "GND") (pinfunction "VSS_GND") (pintype "bidirectional"))
      (node (ref "U$5") (pin "GND") (pinfunction "VSS_GND") (pintype "bidirectional"))
      (node (ref "U$50") (pin "GND") (pinfunction "VSS_GND") (pintype "bidirectional"))
      (node (ref "U$51") (pin "GND") (pinfunction "VSS_GND") (pintype "bidirectional"))
      (node (ref "U$52") (pin "GND") (pinfunction "VSS_GND") (pintype "bidirectional"))
      (node (ref "U$53") (pin "GND") (pinfunction "VSS_GND") (pintype "bidirectional"))
      (node (ref "U$54") (pin "GND") (pinfunction "VSS_GND") (pintype "bidirectional"))
      (node (ref "U$55") (pin "GND") (pinfunction "VSS_GND") (pintype "bidirectional"))
      (node (ref "U$56") (pin "GND") (pinfunction "VSS_GND") (pintype "bidirectional"))
      (node (ref "U$57") (pin "GND") (pinfunction "VSS_GND") (pintype "bidirectional"))
      (node (ref "U$58") (pin "GND") (pinfunction "VSS_GND") (pintype "bidirectional"))
      (node (ref "U$59") (pin "GND") (pinfunction "VSS_GND") (pintype "bidirectional"))
      (node (ref "U$6") (pin "GND") (pinfunction "VSS_GND") (pintype "bidirectional"))
      (node (ref "U$60") (pin "GND") (pinfunction "VSS_GND") (pintype "bidirectional"))
      (node (ref "U$61") (pin "GND") (pinfunction "VSS_GND") (pintype "bidirectional"))
      (node (ref "U$62") (pin "GND") (pinfunction "VSS_GND") (pintype "bidirectional"))
      (node (ref "U$63") (pin "GND") (pinfunction "VSS_GND") (pintype "bidirectional"))
      (node (ref "U$64") (pin "GND") (pinfunction "VSS_GND") (pintype "bidirectional"))
      (node (ref "U$65") (pin "GND") (pinfunction "VSS_GND") (pintype "bidirectional"))
      (node (ref "U$66") (pin "GND") (pinfunction "VSS_GND") (pintype "bidirectional"))
      (node (ref "U$67") (pin "GND") (pinfunction "VSS_GND") (pintype "bidirectional"))
      (node (ref "U$68") (pin "GND") (pinfunction "VSS_GND") (pintype "bidirectional"))
      (node (ref "U$69") (pin "GND") (pinfunction "VSS_GND") (pintype "bidirectional"))
      (node (ref "U$7") (pin "GND") (pinfunction "VSS_GND") (pintype "bidirectional"))
      (node (ref "U$70") (pin "GND") (pinfunction "VSS_GND") (pintype "bidirectional"))
      (node (ref "U$71") (pin "GND") (pinfunction "VSS_GND") (pintype "bidirectional"))
      (node (ref "U$72") (pin "GND") (pinfunction "VSS_GND") (pintype "bidirectional"))
      (node (ref "U$73") (pin "GND") (pinfunction "VSS_GND") (pintype "bidirectional"))
      (node (ref "U$74") (pin "GND") (pinfunction "VSS_GND") (pintype "bidirectional"))
      (node (ref "U$75") (pin "GND") (pinfunction "VSS_GND") (pintype "bidirectional"))
      (node (ref "U$76") (pin "GND") (pinfunction "VSS_GND") (pintype "bidirectional"))
      (node (ref "U$77") (pin "GND") (pinfunction "VSS_GND") (pintype "bidirectional"))
      (node (ref "U$78") (pin "GND") (pinfunction "VSS_GND") (pintype "bidirectional"))
      (node (ref "U$79") (pin "GND") (pinfunction "VSS_GND") (pintype "bidirectional"))
      (node (ref "U$8") (pin "GND") (pinfunction "VSS_GND") (pintype "bidirectional"))
      (node (ref "U$80") (pin "GND") (pinfunction "VSS_GND") (pintype "bidirectional"))
      (node (ref "U$81") (pin "GND") (pinfunction "VSS_GND") (pintype "bidirectional"))
      (node (ref "U$82") (pin "GND") (pinfunction "VSS_GND") (pintype "bidirectional"))
      (node (ref "U$83") (pin "GND") (pinfunction "VSS_GND") (pintype "bidirectional"))
      (node (ref "U$84") (pin "GND") (pinfunction "VSS_GND") (pintype "bidirectional"))
      (node (ref "U$85") (pin "GND") (pinfunction "VSS_GND") (pintype "bidirectional"))
      (node (ref "U$86") (pin "GND") (pinfunction "VSS_GND") (pintype "bidirectional"))
      (node (ref "U$87") (pin "GND") (pinfunction "VSS_GND") (pintype "bidirectional"))
      (node (ref "U$88") (pin "GND") (pinfunction "VSS_GND") (pintype "bidirectional"))
      (node (ref "U$89") (pin "GND") (pinfunction "VSS_GND") (pintype "bidirectional"))
      (node (ref "U$9") (pin "GND") (pinfunction "VSS_GND") (pintype "bidirectional"))
      (node (ref "U$90") (pin "GND") (pinfunction "VSS_GND") (pintype "bidirectional"))
      (node (ref "U$91") (pin "GND") (pinfunction "VSS_GND") (pintype "bidirectional"))
      (node (ref "U$92") (pin "GND") (pinfunction "VSS_GND") (pintype "bidirectional"))
      (node (ref "U$93") (pin "GND") (pinfunction "VSS_GND") (pintype "bidirectional"))
      (node (ref "U$94") (pin "GND") (pinfunction "VSS_GND") (pintype "bidirectional"))
      (node (ref "U$95") (pin "GND") (pinfunction "VSS_GND") (pintype "bidirectional"))
      (node (ref "U$96") (pin "GND") (pinfunction "VSS_GND") (pintype "bidirectional"))
      (node (ref "U$97") (pin "GND") (pinfunction "VSS_GND") (pintype "bidirectional"))
      (node (ref "U$98") (pin "GND") (pinfunction "VSS_GND") (pintype "bidirectional"))
      (node (ref "U$99") (pin "GND") (pinfunction "VSS_GND") (pintype "bidirectional"))
    )
    (net (code "4") (name "Net-(R1-Pad2)") (class "Default")
      (node (ref "R1") (pin "2") (pinfunction "2_2") (pintype "passive"))
      (node (ref "U$1") (pin "DIN") (pinfunction "DIN_DIN") (pintype "bidirectional"))
    )
    (net (code "5") (name "Net-(U$1-PadDOUT)") (class "Default")
      (node (ref "U$1") (pin "DOUT") (pinfunction "DOUT_DOUT") (pintype "bidirectional"))
      (node (ref "U$2") (pin "DIN") (pinfunction "DIN_DIN") (pintype "bidirectional"))
    )
    (net (code "6") (name "Net-(U$2-PadDOUT)") (class "Default")
      (node (ref "U$2") (pin "DOUT") (pinfunction "DOUT_DOUT") (pintype "bidirectional"))
      (node (ref "U$3") (pin "DIN") (pinfunction "DIN_DIN") (pintype "bidirectional"))
    )
    (net (code "7") (name "Net-(U$3-PadDOUT)") (class "Default")
      (node (ref "U$3") (pin "DOUT") (pinfunction "DOUT_DOUT") (pintype "bidirectional"))
      (node (ref "U$4") (pin "DIN") (pinfunction "DIN_DIN") (pintype "bidirectional"))
    )
    (net (code "8") (name "Net-(U$4-PadDOUT)") (class "Default")
      (node (ref "U$4") (pin "DOUT") (pinfunction "DOUT_DOUT") (pintype "bidirectional"))
      (node (ref "U$5") (pin "DIN") (pinfunction "DIN_DIN") (pintype "bidirectional"))
    )
    (net (code "9") (name "Net-(U$5-PadDOUT)") (class "Default")
      (node (ref "U$5") (pin "DOUT") (pinfunction "DOUT_DOUT") (pintype "bidirectional"))
      (node (ref "U$6") (pin "DIN") (pinfunction "DIN_DIN") (pintype "bidirectional"))
    )
    (net (code "10") (name "Net-(U$6-PadDOUT)") (class "Default")
      (node (ref "U$6") (pin "DOUT") (pinfunction "DOUT_DOUT") (pintype "bidirectional"))
      (node (ref "U$7") (pin "DIN") (pinfunction "DIN_DIN") (pintype "bidirectional"))
    )
    (net (code "11") (name "Net-(U$7-PadDOUT)") (class "Default")
      (node (ref "U$7") (pin "DOUT") (pinfunction "DOUT_DOUT") (pintype "bidirectional"))
      (node (ref "U$8") (pin "DIN") (pinfunction "DIN_DIN") (pintype "bidirectional"))
    )
    (net (code "12") (name "Net-(U$8-PadDOUT)") (class "Default")
      (node (ref "U$8") (pin "DOUT") (pinfunction "DOUT_DOUT") (pintype "bidirectional"))
      (node (ref "U$9") (pin "DIN") (pinfunction "DIN_DIN") (pintype "bidirectional"))
    )
    (net (code "13") (name "Net-(U$10-PadDIN)") (class "Default")
      (node (ref "U$10") (pin "DIN") (pinfunction "DIN_DIN") (pintype "bidirectional"))
      (node (ref "U$9") (pin "DOUT") (pinfunction "DOUT_DOUT") (pintype "bidirectional"))
    )
    (net (code "14") (name "Net-(U$10-PadDOUT)") (class "Default")
      (node (ref "U$10") (pin "DOUT") (pinfunction "DOUT_DOUT") (pintype "bidirectional"))
      (node (ref "U$11") (pin "DIN") (pinfunction "DIN_DIN") (pintype "bidirectional"))
    )
    (net (code "15") (name "Net-(U$11-PadDOUT)") (class "Default")
      (node (ref "U$11") (pin "DOUT") (pinfunction "DOUT_DOUT") (pintype "bidirectional"))
      (node (ref "U$12") (pin "DIN") (pinfunction "DIN_DIN") (pintype "bidirectional"))
    )
    (net (code "16") (name "Net-(U$12-PadDOUT)") (class "Default")
      (node (ref "U$12") (pin "DOUT") (pinfunction "DOUT_DOUT") (pintype "bidirectional"))
      (node (ref "U$13") (pin "DIN") (pinfunction "DIN_DIN") (pintype "bidirectional"))
    )
    (net (code "17") (name "Net-(U$13-PadDOUT)") (class "Default")
      (node (ref "U$13") (pin "DOUT") (pinfunction "DOUT_DOUT") (pintype "bidirectional"))
      (node (ref "U$14") (pin "DIN") (pinfunction "DIN_DIN") (pintype "bidirectional"))
    )
    (net (code "18") (name "Net-(U$14-PadDOUT)") (class "Default")
      (node (ref "U$14") (pin "DOUT") (pinfunction "DOUT_DOUT") (pintype "bidirectional"))
      (node (ref "U$15") (pin "DIN") (pinfunction "DIN_DIN") (pintype "bidirectional"))
    )
    (net (code "19") (name "Net-(U$15-PadDOUT)") (class "Default")
      (node (ref "U$15") (pin "DOUT") (pinfunction "DOUT_DOUT") (pintype "bidirectional"))
      (node (ref "U$16") (pin "DIN") (pinfunction "DIN_DIN") (pintype "bidirectional"))
    )
    (net (code "20") (name "Net-(U$16-PadDOUT)") (class "Default")
      (node (ref "U$16") (pin "DOUT") (pinfunction "DOUT_DOUT") (pintype "bidirectional"))
      (node (ref "U$17") (pin "DIN") (pinfunction "DIN_DIN") (pintype "bidirectional"))
    )
    (net (code "21") (name "Net-(U$17-PadDOUT)") (class "Default")
      (node (ref "U$17") (pin "DOUT") (pinfunction "DOUT_DOUT") (pintype "bidirectional"))
      (node (ref "U$18") (pin "DIN") (pinfunction "DIN_DIN") (pintype "bidirectional"))
    )
    (net (code "22") (name "Net-(U$18-PadDOUT)") (class "Default")
      (node (ref "U$18") (pin "DOUT") (pinfunction "DOUT_DOUT") (pintype "bidirectional"))
      (node (ref "U$19") (pin "DIN") (pinfunction "DIN_DIN") (pintype "bidirectional"))
    )
    (net (code "23") (name "Net-(U$19-PadDOUT)") (class "Default")
      (node (ref "U$19") (pin "DOUT") (pinfunction "DOUT_DOUT") (pintype "bidirectional"))
      (node (ref "U$20") (pin "DIN") (pinfunction "DIN_DIN") (pintype "bidirectional"))
    )
    (net (code "24") (name "Net-(U$20-PadDOUT)") (class "Default")
      (node (ref "U$20") (pin "DOUT") (pinfunction "DOUT_DOUT") (pintype "bidirectional"))
      (node (ref "U$21") (pin "DIN") (pinfunction "DIN_DIN") (pintype "bidirectional"))
    )
    (net (code "25") (name "Net-(U$21-PadDOUT)") (class "Default")
      (node (ref "U$21") (pin "DOUT") (pinfunction "DOUT_DOUT") (pintype "bidirectional"))
      (node (ref "U$22") (pin "DIN") (pinfunction "DIN_DIN") (pintype "bidirectional"))
    )
    (net (code "26") (name "Net-(U$22-PadDOUT)") (class "Default")
      (node (ref "U$22") (pin "DOUT") (pinfunction "DOUT_DOUT") (pintype "bidirectional"))
      (node (ref "U$23") (pin "DIN") (pinfunction "DIN_DIN") (pintype "bidirectional"))
    )
    (net (code "27") (name "Net-(U$23-PadDOUT)") (class "Default")
      (node (ref "U$23") (pin "DOUT") (pinfunction "DOUT_DOUT") (pintype "bidirectional"))
      (node (ref "U$24") (pin "DIN") (pinfunction "DIN_DIN") (pintype "bidirectional"))
    )
    (net (code "28") (name "Net-(U$24-PadDOUT)") (class "Default")
      (node (ref "U$24") (pin "DOUT") (pinfunction "DOUT_DOUT") (pintype "bidirectional"))
      (node (ref "U$25") (pin "DIN") (pinfunction "DIN_DIN") (pintype "bidirectional"))
    )
    (net (code "29") (name "Net-(U$25-PadDOUT)") (class "Default")
      (node (ref "U$25") (pin "DOUT") (pinfunction "DOUT_DOUT") (pintype "bidirectional"))
      (node (ref "U$26") (pin "DIN") (pinfunction "DIN_DIN") (pintype "bidirectional"))
    )
    (net (code "30") (name "Net-(U$26-PadDOUT)") (class "Default")
      (node (ref "U$26") (pin "DOUT") (pinfunction "DOUT_DOUT") (pintype "bidirectional"))
      (node (ref "U$27") (pin "DIN") (pinfunction "DIN_DIN") (pintype "bidirectional"))
    )
    (net (code "31") (name "Net-(U$27-PadDOUT)") (class "Default")
      (node (ref "U$27") (pin "DOUT") (pinfunction "DOUT_DOUT") (pintype "bidirectional"))
      (node (ref "U$28") (pin "DIN") (pinfunction "DIN_DIN") (pintype "bidirectional"))
    )
    (net (code "32") (name "Net-(U$28-PadDOUT)") (class "Default")
      (node (ref "U$28") (pin "DOUT") (pinfunction "DOUT_DOUT") (pintype "bidirectional"))
      (node (ref "U$29") (pin "DIN") (pinfunction "DIN_DIN") (pintype "bidirectional"))
    )
    (net (code "33") (name "Net-(U$29-PadDOUT)") (class "Default")
      (node (ref "U$29") (pin "DOUT") (pinfunction "DOUT_DOUT") (pintype "bidirectional"))
      (node (ref "U$30") (pin "DIN") (pinfunction "DIN_DIN") (pintype "bidirectional"))
    )
    (net (code "34") (name "Net-(U$30-PadDOUT)") (class "Default")
      (node (ref "U$30") (pin "DOUT") (pinfunction "DOUT_DOUT") (pintype "bidirectional"))
      (node (ref "U$31") (pin "DIN") (pinfunction "DIN_DIN") (pintype "bidirectional"))
    )
    (net (code "35") (name "Net-(U$31-PadDOUT)") (class "Default")
      (node (ref "U$31") (pin "DOUT") (pinfunction "DOUT_DOUT") (pintype "bidirectional"))
      (node (ref "U$32") (pin "DIN") (pinfunction "DIN_DIN") (pintype "bidirectional"))
    )
    (net (code "36") (name "Net-(U$32-PadDOUT)") (class "Default")
      (node (ref "U$32") (pin "DOUT") (pinfunction "DOUT_DOUT") (pintype "bidirectional"))
      (node (ref "U$33") (pin "DIN") (pinfunction "DIN_DIN") (pintype "bidirectional"))
    )
    (net (code "37") (name "Net-(U$33-PadDOUT)") (class "Default")
      (node (ref "U$33") (pin "DOUT") (pinfunction "DOUT_DOUT") (pintype "bidirectional"))
      (node (ref "U$34") (pin "DIN") (pinfunction "DIN_DIN") (pintype "bidirectional"))
    )
    (net (code "38") (name "Net-(U$34-PadDOUT)") (class "Default")
      (node (ref "U$34") (pin "DOUT") (pinfunction "DOUT_DOUT") (pintype "bidirectional"))
      (node (ref "U$35") (pin "DIN") (pinfunction "DIN_DIN") (pintype "bidirectional"))
    )
    (net (code "39") (name "Net-(U$35-PadDOUT)") (class "Default")
      (node (ref "U$35") (pin "DOUT") (pinfunction "DOUT_DOUT") (pintype "bidirectional"))
      (node (ref "U$36") (pin "DIN") (pinfunction "DIN_DIN") (pintype "bidirectional"))
    )
    (net (code "40") (name "Net-(U$36-PadDOUT)") (class "Default")
      (node (ref "U$36") (pin "DOUT") (pinfunction "DOUT_DOUT") (pintype "bidirectional"))
      (node (ref "U$37") (pin "DIN") (pinfunction "DIN_DIN") (pintype "bidirectional"))
    )
    (net (code "41") (name "Net-(U$37-PadDOUT)") (class "Default")
      (node (ref "U$37") (pin "DOUT") (pinfunction "DOUT_DOUT") (pintype "bidirectional"))
      (node (ref "U$38") (pin "DIN") (pinfunction "DIN_DIN") (pintype "bidirectional"))
    )
    (net (code "42") (name "Net-(U$38-PadDOUT)") (class "Default")
      (node (ref "U$38") (pin "DOUT") (pinfunction "DOUT_DOUT") (pintype "bidirectional"))
      (node (ref "U$39") (pin "DIN") (pinfunction "DIN_DIN") (pintype "bidirectional"))
    )
    (net (code "43") (name "Net-(U$39-PadDOUT)") (class "Default")
      (node (ref "U$39") (pin "DOUT") (pinfunction "DOUT_DOUT") (pintype "bidirectional"))
      (node (ref "U$40") (pin "DIN") (pinfunction "DIN_DIN") (pintype "bidirectional"))
    )
    (net (code "44") (name "Net-(U$40-PadDOUT)") (class "Default")
      (node (ref "U$40") (pin "DOUT") (pinfunction "DOUT_DOUT") (pintype "bidirectional"))
      (node (ref "U$41") (pin "DIN") (pinfunction "DIN_DIN") (pintype "bidirectional"))
    )
    (net (code "45") (name "Net-(U$41-PadDOUT)") (class "Default")
      (node (ref "U$41") (pin "DOUT") (pinfunction "DOUT_DOUT") (pintype "bidirectional"))
      (node (ref "U$42") (pin "DIN") (pinfunction "DIN_DIN") (pintype "bidirectional"))
    )
    (net (code "46") (name "Net-(U$42-PadDOUT)") (class "Default")
      (node (ref "U$42") (pin "DOUT") (pinfunction "DOUT_DOUT") (pintype "bidirectional"))
      (node (ref "U$43") (pin "DIN") (pinfunction "DIN_DIN") (pintype "bidirectional"))
    )
    (net (code "47") (name "Net-(U$43-PadDOUT)") (class "Default")
      (node (ref "U$43") (pin "DOUT") (pinfunction "DOUT_DOUT") (pintype "bidirectional"))
      (node (ref "U$44") (pin "DIN") (pinfunction "DIN_DIN") (pintype "bidirectional"))
    )
    (net (code "48") (name "Net-(U$44-PadDOUT)") (class "Default")
      (node (ref "U$44") (pin "DOUT") (pinfunction "DOUT_DOUT") (pintype "bidirectional"))
      (node (ref "U$45") (pin "DIN") (pinfunction "DIN_DIN") (pintype "bidirectional"))
    )
    (net (code "49") (name "Net-(U$45-PadDOUT)") (class "Default")
      (node (ref "U$45") (pin "DOUT") (pinfunction "DOUT_DOUT") (pintype "bidirectional"))
      (node (ref "U$46") (pin "DIN") (pinfunction "DIN_DIN") (pintype "bidirectional"))
    )
    (net (code "50") (name "Net-(U$46-PadDOUT)") (class "Default")
      (node (ref "U$46") (pin "DOUT") (pinfunction "DOUT_DOUT") (pintype "bidirectional"))
      (node (ref "U$47") (pin "DIN") (pinfunction "DIN_DIN") (pintype "bidirectional"))
    )
    (net (code "51") (name "Net-(U$47-PadDOUT)") (class "Default")
      (node (ref "U$47") (pin "DOUT") (pinfunction "DOUT_DOUT") (pintype "bidirectional"))
      (node (ref "U$48") (pin "DIN") (pinfunction "DIN_DIN") (pintype "bidirectional"))
    )
    (net (code "52") (name "Net-(U$48-PadDOUT)") (class "Default")
      (node (ref "U$48") (pin "DOUT") (pinfunction "DOUT_DOUT") (pintype "bidirectional"))
      (node (ref "U$49") (pin "DIN") (pinfunction "DIN_DIN") (pintype "bidirectional"))
    )
    (net (code "53") (name "Net-(U$49-PadDOUT)") (class "Default")
      (node (ref "U$49") (pin "DOUT") (pinfunction "DOUT_DOUT") (pintype "bidirectional"))
      (node (ref "U$50") (pin "DIN") (pinfunction "DIN_DIN") (pintype "bidirectional"))
    )
    (net (code "54") (name "Net-(U$50-PadDOUT)") (class "Default")
      (node (ref "U$50") (pin "DOUT") (pinfunction "DOUT_DOUT") (pintype "bidirectional"))
      (node (ref "U$51") (pin "DIN") (pinfunction "DIN_DIN") (pintype "bidirectional"))
    )
    (net (code "55") (name "Net-(U$51-PadDOUT)") (class "Default")
      (node (ref "U$51") (pin "DOUT") (pinfunction "DOUT_DOUT") (pintype "bidirectional"))
      (node (ref "U$52") (pin "DIN") (pinfunction "DIN_DIN") (pintype "bidirectional"))
    )
    (net (code "56") (name "Net-(U$52-PadDOUT)") (class "Default")
      (node (ref "U$52") (pin "DOUT") (pinfunction "DOUT_DOUT") (pintype "bidirectional"))
      (node (ref "U$66") (pin "DIN") (pinfunction "DIN_DIN") (pintype "bidirectional"))
    )
    (net (code "57") (name "Net-(U$53-PadDIN)") (class "Default")
      (node (ref "U$53") (pin "DIN") (pinfunction "DIN_DIN") (pintype "bidirectional"))
      (node (ref "U$65") (pin "DOUT") (pinfunction "DOUT_DOUT") (pintype "bidirectional"))
    )
    (net (code "58") (name "Net-(U$53-PadDOUT)") (class "Default")
      (node (ref "U$53") (pin "DOUT") (pinfunction "DOUT_DOUT") (pintype "bidirectional"))
      (node (ref "U$54") (pin "DIN") (pinfunction "DIN_DIN") (pintype "bidirectional"))
    )
    (net (code "59") (name "Net-(U$54-PadDOUT)") (class "Default")
      (node (ref "U$54") (pin "DOUT") (pinfunction "DOUT_DOUT") (pintype "bidirectional"))
      (node (ref "U$55") (pin "DIN") (pinfunction "DIN_DIN") (pintype "bidirectional"))
    )
    (net (code "60") (name "Net-(U$55-PadDOUT)") (class "Default")
      (node (ref "U$55") (pin "DOUT") (pinfunction "DOUT_DOUT") (pintype "bidirectional"))
      (node (ref "U$56") (pin "DIN") (pinfunction "DIN_DIN") (pintype "bidirectional"))
    )
    (net (code "61") (name "Net-(U$56-PadDOUT)") (class "Default")
      (node (ref "U$56") (pin "DOUT") (pinfunction "DOUT_DOUT") (pintype "bidirectional"))
      (node (ref "U$57") (pin "DIN") (pinfunction "DIN_DIN") (pintype "bidirectional"))
    )
    (net (code "62") (name "Net-(U$57-PadDOUT)") (class "Default")
      (node (ref "U$57") (pin "DOUT") (pinfunction "DOUT_DOUT") (pintype "bidirectional"))
      (node (ref "U$58") (pin "DIN") (pinfunction "DIN_DIN") (pintype "bidirectional"))
    )
    (net (code "63") (name "Net-(U$58-PadDOUT)") (class "Default")
      (node (ref "U$58") (pin "DOUT") (pinfunction "DOUT_DOUT") (pintype "bidirectional"))
      (node (ref "U$59") (pin "DIN") (pinfunction "DIN_DIN") (pintype "bidirectional"))
    )
    (net (code "64") (name "Net-(U$59-PadDOUT)") (class "Default")
      (node (ref "U$59") (pin "DOUT") (pinfunction "DOUT_DOUT") (pintype "bidirectional"))
      (node (ref "U$60") (pin "DIN") (pinfunction "DIN_DIN") (pintype "bidirectional"))
    )
    (net (code "65") (name "Net-(U$60-PadDOUT)") (class "Default")
      (node (ref "U$60") (pin "DOUT") (pinfunction "DOUT_DOUT") (pintype "bidirectional"))
      (node (ref "U$74") (pin "DIN") (pinfunction "DIN_DIN") (pintype "bidirectional"))
    )
    (net (code "66") (name "Net-(U$61-PadDIN)") (class "Default")
      (node (ref "U$61") (pin "DIN") (pinfunction "DIN_DIN") (pintype "bidirectional"))
      (node (ref "U$73") (pin "DOUT") (pinfunction "DOUT_DOUT") (pintype "bidirectional"))
    )
    (net (code "67") (name "Net-(U$61-PadDOUT)") (class "Default")
      (node (ref "U$61") (pin "DOUT") (pinfunction "DOUT_DOUT") (pintype "bidirectional"))
      (node (ref "U$62") (pin "DIN") (pinfunction "DIN_DIN") (pintype "bidirectional"))
    )
    (net (code "68") (name "Net-(U$62-PadDOUT)") (class "Default")
      (node (ref "U$62") (pin "DOUT") (pinfunction "DOUT_DOUT") (pintype "bidirectional"))
      (node (ref "U$63") (pin "DIN") (pinfunction "DIN_DIN") (pintype "bidirectional"))
    )
    (net (code "69") (name "Net-(U$63-PadDOUT)") (class "Default")
      (node (ref "U$63") (pin "DOUT") (pinfunction "DOUT_DOUT") (pintype "bidirectional"))
      (node (ref "U$64") (pin "DIN") (pinfunction "DIN_DIN") (pintype "bidirectional"))
    )
    (net (code "70") (name "Net-(U$64-PadDOUT)") (class "Default")
      (node (ref "U$64") (pin "DOUT") (pinfunction "DOUT_DOUT") (pintype "bidirectional"))
      (node (ref "U$65") (pin "DIN") (pinfunction "DIN_DIN") (pintype "bidirectional"))
    )
    (net (code "71") (name "Net-(U$66-PadDOUT)") (class "Default")
      (node (ref "U$66") (pin "DOUT") (pinfunction "DOUT_DOUT") (pintype "bidirectional"))
      (node (ref "U$67") (pin "DIN") (pinfunction "DIN_DIN") (pintype "bidirectional"))
    )
    (net (code "72") (name "Net-(U$67-PadDOUT)") (class "Default")
      (node (ref "U$67") (pin "DOUT") (pinfunction "DOUT_DOUT") (pintype "bidirectional"))
      (node (ref "U$68") (pin "DIN") (pinfunction "DIN_DIN") (pintype "bidirectional"))
    )
    (net (code "73") (name "Net-(U$68-PadDOUT)") (class "Default")
      (node (ref "U$68") (pin "DOUT") (pinfunction "DOUT_DOUT") (pintype "bidirectional"))
      (node (ref "U$69") (pin "DIN") (pinfunction "DIN_DIN") (pintype "bidirectional"))
    )
    (net (code "74") (name "Net-(U$69-PadDOUT)") (class "Default")
      (node (ref "U$69") (pin "DOUT") (pinfunction "DOUT_DOUT") (pintype "bidirectional"))
      (node (ref "U$70") (pin "DIN") (pinfunction "DIN_DIN") (pintype "bidirectional"))
    )
    (net (code "75") (name "Net-(U$70-PadDOUT)") (class "Default")
      (node (ref "U$70") (pin "DOUT") (pinfunction "DOUT_DOUT") (pintype "bidirectional"))
      (node (ref "U$71") (pin "DIN") (pinfunction "DIN_DIN") (pintype "bidirectional"))
    )
    (net (code "76") (name "Net-(U$71-PadDOUT)") (class "Default")
      (node (ref "U$71") (pin "DOUT") (pinfunction "DOUT_DOUT") (pintype "bidirectional"))
      (node (ref "U$72") (pin "DIN") (pinfunction "DIN_DIN") (pintype "bidirectional"))
    )
    (net (code "77") (name "Net-(U$72-PadDOUT)") (class "Default")
      (node (ref "U$72") (pin "DOUT") (pinfunction "DOUT_DOUT") (pintype "bidirectional"))
      (node (ref "U$73") (pin "DIN") (pinfunction "DIN_DIN") (pintype "bidirectional"))
    )
    (net (code "78") (name "Net-(U$74-PadDOUT)") (class "Default")
      (node (ref "U$74") (pin "DOUT") (pinfunction "DOUT_DOUT") (pintype "bidirectional"))
      (node (ref "U$75") (pin "DIN") (pinfunction "DIN_DIN") (pintype "bidirectional"))
    )
    (net (code "79") (name "Net-(U$75-PadDOUT)") (class "Default")
      (node (ref "U$75") (pin "DOUT") (pinfunction "DOUT_DOUT") (pintype "bidirectional"))
      (node (ref "U$76") (pin "DIN") (pinfunction "DIN_DIN") (pintype "bidirectional"))
    )
    (net (code "80") (name "Net-(U$76-PadDOUT)") (class "Default")
      (node (ref "U$76") (pin "DOUT") (pinfunction "DOUT_DOUT") (pintype "bidirectional"))
      (node (ref "U$77") (pin "DIN") (pinfunction "DIN_DIN") (pintype "bidirectional"))
    )
    (net (code "81") (name "Net-(U$77-PadDOUT)") (class "Default")
      (node (ref "U$77") (pin "DOUT") (pinfunction "DOUT_DOUT") (pintype "bidirectional"))
      (node (ref "U$78") (pin "DIN") (pinfunction "DIN_DIN") (pintype "bidirectional"))
    )
    (net (code "82") (name "Net-(U$78-PadDOUT)") (class "Default")
      (node (ref "U$78") (pin "DOUT") (pinfunction "DOUT_DOUT") (pintype "bidirectional"))
      (node (ref "U$79") (pin "DIN") (pinfunction "DIN_DIN") (pintype "bidirectional"))
    )
    (net (code "83") (name "Net-(U$79-PadDOUT)") (class "Default")
      (node (ref "U$79") (pin "DOUT") (pinfunction "DOUT_DOUT") (pintype "bidirectional"))
      (node (ref "U$80") (pin "DIN") (pinfunction "DIN_DIN") (pintype "bidirectional"))
    )
    (net (code "84") (name "Net-(U$80-PadDOUT)") (class "Default")
      (node (ref "U$80") (pin "DOUT") (pinfunction "DOUT_DOUT") (pintype "bidirectional"))
      (node (ref "U$81") (pin "DIN") (pinfunction "DIN_DIN") (pintype "bidirectional"))
    )
    (net (code "85") (name "Net-(U$81-PadDOUT)") (class "Default")
      (node (ref "U$81") (pin "DOUT") (pinfunction "DOUT_DOUT") (pintype "bidirectional"))
      (node (ref "U$82") (pin "DIN") (pinfunction "DIN_DIN") (pintype "bidirectional"))
    )
    (net (code "86") (name "Net-(U$82-PadDOUT)") (class "Default")
      (node (ref "U$82") (pin "DOUT") (pinfunction "DOUT_DOUT") (pintype "bidirectional"))
      (node (ref "U$83") (pin "DIN") (pinfunction "DIN_DIN") (pintype "bidirectional"))
    )
    (net (code "87") (name "Net-(U$83-PadDOUT)") (class "Default")
      (node (ref "U$83") (pin "DOUT") (pinfunction "DOUT_DOUT") (pintype "bidirectional"))
      (node (ref "U$84") (pin "DIN") (pinfunction "DIN_DIN") (pintype "bidirectional"))
    )
    (net (code "88") (name "Net-(U$84-PadDOUT)") (class "Default")
      (node (ref "U$84") (pin "DOUT") (pinfunction "DOUT_DOUT") (pintype "bidirectional"))
      (node (ref "U$85") (pin "DIN") (pinfunction "DIN_DIN") (pintype "bidirectional"))
    )
    (net (code "89") (name "Net-(U$85-PadDOUT)") (class "Default")
      (node (ref "U$85") (pin "DOUT") (pinfunction "DOUT_DOUT") (pintype "bidirectional"))
      (node (ref "U$86") (pin "DIN") (pinfunction "DIN_DIN") (pintype "bidirectional"))
    )
    (net (code "90") (name "Net-(U$86-PadDOUT)") (class "Default")
      (node (ref "U$86") (pin "DOUT") (pinfunction "DOUT_DOUT") (pintype "bidirectional"))
      (node (ref "U$87") (pin "DIN") (pinfunction "DIN_DIN") (pintype "bidirectional"))
    )
    (net (code "91") (name "Net-(U$87-PadDOUT)") (class "Default")
      (node (ref "U$87") (pin "DOUT") (pinfunction "DOUT_DOUT") (pintype "bidirectional"))
      (node (ref "U$88") (pin "DIN") (pinfunction "DIN_DIN") (pintype "bidirectional"))
    )
    (net (code "92") (name "Net-(U$88-PadDOUT)") (class "Default")
      (node (ref "U$88") (pin "DOUT") (pinfunction "DOUT_DOUT") (pintype "bidirectional"))
      (node (ref "U$89") (pin "DIN") (pinfunction "DIN_DIN") (pintype "bidirectional"))
    )
    (net (code "93") (name "Net-(U$89-PadDOUT)") (class "Default")
      (node (ref "U$89") (pin "DOUT") (pinfunction "DOUT_DOUT") (pintype "bidirectional"))
      (node (ref "U$90") (pin "DIN") (pinfunction "DIN_DIN") (pintype "bidirectional"))
    )
    (net (code "94") (name "Net-(U$90-PadDOUT)") (class "Default")
      (node (ref "U$90") (pin "DOUT") (pinfunction "DOUT_DOUT") (pintype "bidirectional"))
      (node (ref "U$91") (pin "DIN") (pinfunction "DIN_DIN") (pintype "bidirectional"))
    )
    (net (code "95") (name "Net-(U$91-PadDOUT)") (class "Default")
      (node (ref "U$91") (pin "DOUT") (pinfunction "DOUT_DOUT") (pintype "bidirectional"))
      (node (ref "U$92") (pin "DIN") (pinfunction "DIN_DIN") (pintype "bidirectional"))
    )
    (net (code "96") (name "Net-(U$92-PadDOUT)") (class "Default")
      (node (ref "U$92") (pin "DOUT") (pinfunction "DOUT_DOUT") (pintype "bidirectional"))
      (node (ref "U$93") (pin "DIN") (pinfunction "DIN_DIN") (pintype "bidirectional"))
    )
    (net (code "97") (name "Net-(U$93-PadDOUT)") (class "Default")
      (node (ref "U$93") (pin "DOUT") (pinfunction "DOUT_DOUT") (pintype "bidirectional"))
      (node (ref "U$94") (pin "DIN") (pinfunction "DIN_DIN") (pintype "bidirectional"))
    )
    (net (code "98") (name "Net-(U$94-PadDOUT)") (class "Default")
      (node (ref "U$94") (pin "DOUT") (pinfunction "DOUT_DOUT") (pintype "bidirectional"))
      (node (ref "U$95") (pin "DIN") (pinfunction "DIN_DIN") (pintype "bidirectional"))
    )
    (net (code "99") (name "Net-(U$95-PadDOUT)") (class "Default")
      (node (ref "U$95") (pin "DOUT") (pinfunction "DOUT_DOUT") (pintype "bidirectional"))
      (node (ref "U$96") (pin "DIN") (pinfunction "DIN_DIN") (pintype "bidirectional"))
    )
    (net (code "100") (name "Net-(U$96-PadDOUT)") (class "Default")
      (node (ref "U$96") (pin "DOUT") (pinfunction "DOUT_DOUT") (pintype "bidirectional"))
      (node (ref "U$97") (pin "DIN") (pinfunction "DIN_DIN") (pintype "bidirectional"))
    )
    (net (code "101") (name "Net-(U$97-PadDOUT)") (class "Default")
      (node (ref "U$97") (pin "DOUT") (pinfunction "DOUT_DOUT") (pintype "bidirectional"))
      (node (ref "U$98") (pin "DIN") (pinfunction "DIN_DIN") (pintype "bidirectional"))
    )
    (net (code "102") (name "Net-(U$98-PadDOUT)") (class "Default")
      (node (ref "U$98") (pin "DOUT") (pinfunction "DOUT_DOUT") (pintype "bidirectional"))
      (node (ref "U$99") (pin "DIN") (pinfunction "DIN_DIN") (pintype "bidirectional"))
    )
    (net (code "103") (name "Net-(U$100-PadDIN)") (class "Default")
      (node (ref "U$100") (pin "DIN") (pinfunction "DIN_DIN") (pintype "bidirectional"))
      (node (ref "U$99") (pin "DOUT") (pinfunction "DOUT_DOUT") (pintype "bidirectional"))
    )
    (net (code "104") (name "Net-(U$100-PadDOUT)") (class "Default")
      (node (ref "U$100") (pin "DOUT") (pinfunction "DOUT_DOUT") (pintype "bidirectional"))
      (node (ref "U$101") (pin "DIN") (pinfunction "DIN_DIN") (pintype "bidirectional"))
    )
    (net (code "105") (name "Net-(U$101-PadDOUT)") (class "Default")
      (node (ref "U$101") (pin "DOUT") (pinfunction "DOUT_DOUT") (pintype "bidirectional"))
      (node (ref "U$102") (pin "DIN") (pinfunction "DIN_DIN") (pintype "bidirectional"))
    )
    (net (code "106") (name "Net-(U$102-PadDOUT)") (class "Default")
      (node (ref "U$102") (pin "DOUT") (pinfunction "DOUT_DOUT") (pintype "bidirectional"))
      (node (ref "U$103") (pin "DIN") (pinfunction "DIN_DIN") (pintype "bidirectional"))
    )
    (net (code "107") (name "Net-(U$103-PadDOUT)") (class "Default")
      (node (ref "U$103") (pin "DOUT") (pinfunction "DOUT_DOUT") (pintype "bidirectional"))
      (node (ref "U$104") (pin "DIN") (pinfunction "DIN_DIN") (pintype "bidirectional"))
    )
    (net (code "108") (name "Net-(U$104-PadDOUT)") (class "Default")
      (node (ref "U$104") (pin "DOUT") (pinfunction "DOUT_DOUT") (pintype "bidirectional"))
      (node (ref "U$105") (pin "DIN") (pinfunction "DIN_DIN") (pintype "bidirectional"))
    )
    (net (code "109") (name "Net-(U$105-PadDOUT)") (class "Default")
      (node (ref "U$105") (pin "DOUT") (pinfunction "DOUT_DOUT") (pintype "bidirectional"))
      (node (ref "U$106") (pin "DIN") (pinfunction "DIN_DIN") (pintype "bidirectional"))
    )
    (net (code "110") (name "Net-(U$106-PadDOUT)") (class "Default")
      (node (ref "U$106") (pin "DOUT") (pinfunction "DOUT_DOUT") (pintype "bidirectional"))
      (node (ref "U$107") (pin "DIN") (pinfunction "DIN_DIN") (pintype "bidirectional"))
    )
    (net (code "111") (name "Net-(U$107-PadDOUT)") (class "Default")
      (node (ref "U$107") (pin "DOUT") (pinfunction "DOUT_DOUT") (pintype "bidirectional"))
      (node (ref "U$108") (pin "DIN") (pinfunction "DIN_DIN") (pintype "bidirectional"))
    )
    (net (code "112") (name "Net-(U$108-PadDOUT)") (class "Default")
      (node (ref "U$108") (pin "DOUT") (pinfunction "DOUT_DOUT") (pintype "bidirectional"))
      (node (ref "U$109") (pin "DIN") (pinfunction "DIN_DIN") (pintype "bidirectional"))
    )
    (net (code "113") (name "Net-(U$109-PadDOUT)") (class "Default")
      (node (ref "U$109") (pin "DOUT") (pinfunction "DOUT_DOUT") (pintype "bidirectional"))
      (node (ref "U$110") (pin "DIN") (pinfunction "DIN_DIN") (pintype "bidirectional"))
    )
    (net (code "114") (name "Net-(U$110-PadDOUT)") (class "Default")
      (node (ref "U$110") (pin "DOUT") (pinfunction "DOUT_DOUT") (pintype "bidirectional"))
      (node (ref "U$111") (pin "DIN") (pinfunction "DIN_DIN") (pintype "bidirectional"))
    )
    (net (code "115") (name "Net-(U$111-PadDOUT)") (class "Default")
      (node (ref "U$111") (pin "DOUT") (pinfunction "DOUT_DOUT") (pintype "bidirectional"))
      (node (ref "U$112") (pin "DIN") (pinfunction "DIN_DIN") (pintype "bidirectional"))
    )
    (net (code "116") (name "Net-(U$112-PadDOUT)") (class "Default")
      (node (ref "U$112") (pin "DOUT") (pinfunction "DOUT_DOUT") (pintype "bidirectional"))
      (node (ref "U$113") (pin "DIN") (pinfunction "DIN_DIN") (pintype "bidirectional"))
    )
    (net (code "117") (name "Net-(U$113-PadDOUT)") (class "Default")
      (node (ref "U$113") (pin "DOUT") (pinfunction "DOUT_DOUT") (pintype "bidirectional"))
      (node (ref "U$114") (pin "DIN") (pinfunction "DIN_DIN") (pintype "bidirectional"))
    )
    (net (code "118") (name "Net-(U$114-PadDOUT)") (class "Default")
      (node (ref "U$114") (pin "DOUT") (pinfunction "DOUT_DOUT") (pintype "bidirectional"))
      (node (ref "U$115") (pin "DIN") (pinfunction "DIN_DIN") (pintype "bidirectional"))
    )
    (net (code "119") (name "Net-(U$115-PadDOUT)") (class "Default")
      (node (ref "U$115") (pin "DOUT") (pinfunction "DOUT_DOUT") (pintype "bidirectional"))
      (node (ref "U$116") (pin "DIN") (pinfunction "DIN_DIN") (pintype "bidirectional"))
    )
    (net (code "120") (name "Net-(U$116-PadDOUT)") (class "Default")
      (node (ref "U$116") (pin "DOUT") (pinfunction "DOUT_DOUT") (pintype "bidirectional"))
      (node (ref "U$117") (pin "DIN") (pinfunction "DIN_DIN") (pintype "bidirectional"))
    )
    (net (code "121") (name "Net-(U$117-PadDOUT)") (class "Default")
      (node (ref "U$117") (pin "DOUT") (pinfunction "DOUT_DOUT") (pintype "bidirectional"))
      (node (ref "U$118") (pin "DIN") (pinfunction "DIN_DIN") (pintype "bidirectional"))
    )
    (net (code "122") (name "Net-(U$118-PadDOUT)") (class "Default")
      (node (ref "U$118") (pin "DOUT") (pinfunction "DOUT_DOUT") (pintype "bidirectional"))
      (node (ref "U$119") (pin "DIN") (pinfunction "DIN_DIN") (pintype "bidirectional"))
    )
    (net (code "123") (name "Net-(U$119-PadDOUT)") (class "Default")
      (node (ref "U$119") (pin "DOUT") (pinfunction "DOUT_DOUT") (pintype "bidirectional"))
      (node (ref "U$120") (pin "DIN") (pinfunction "DIN_DIN") (pintype "bidirectional"))
    )
    (net (code "124") (name "Net-(U$120-PadDOUT)") (class "Default")
      (node (ref "U$120") (pin "DOUT") (pinfunction "DOUT_DOUT") (pintype "bidirectional"))
      (node (ref "U$121") (pin "DIN") (pinfunction "DIN_DIN") (pintype "bidirectional"))
    )
    (net (code "125") (name "Net-(U$121-PadDOUT)") (class "Default")
      (node (ref "U$121") (pin "DOUT") (pinfunction "DOUT_DOUT") (pintype "bidirectional"))
      (node (ref "U$122") (pin "DIN") (pinfunction "DIN_DIN") (pintype "bidirectional"))
    )
    (net (code "126") (name "Net-(U$122-PadDOUT)") (class "Default")
      (node (ref "U$122") (pin "DOUT") (pinfunction "DOUT_DOUT") (pintype "bidirectional"))
      (node (ref "U$123") (pin "DIN") (pinfunction "DIN_DIN") (pintype "bidirectional"))
    )
    (net (code "127") (name "Net-(U$123-PadDOUT)") (class "Default")
      (node (ref "U$123") (pin "DOUT") (pinfunction "DOUT_DOUT") (pintype "bidirectional"))
      (node (ref "U$124") (pin "DIN") (pinfunction "DIN_DIN") (pintype "bidirectional"))
    )
    (net (code "128") (name "Net-(U$124-PadDOUT)") (class "Default")
      (node (ref "U$124") (pin "DOUT") (pinfunction "DOUT_DOUT") (pintype "bidirectional"))
      (node (ref "U$125") (pin "DIN") (pinfunction "DIN_DIN") (pintype "bidirectional"))
    )
    (net (code "129") (name "unconnected-(U$125-PadDOUT)") (class "Default")
      (node (ref "U$125") (pin "DOUT") (pinfunction "DOUT_DOUT") (pintype "bidirectional"))
    )
  )
)
